# zx80_SD_12_smd_build003.net
KiCad netlist of a schematic drawn in EAGLE
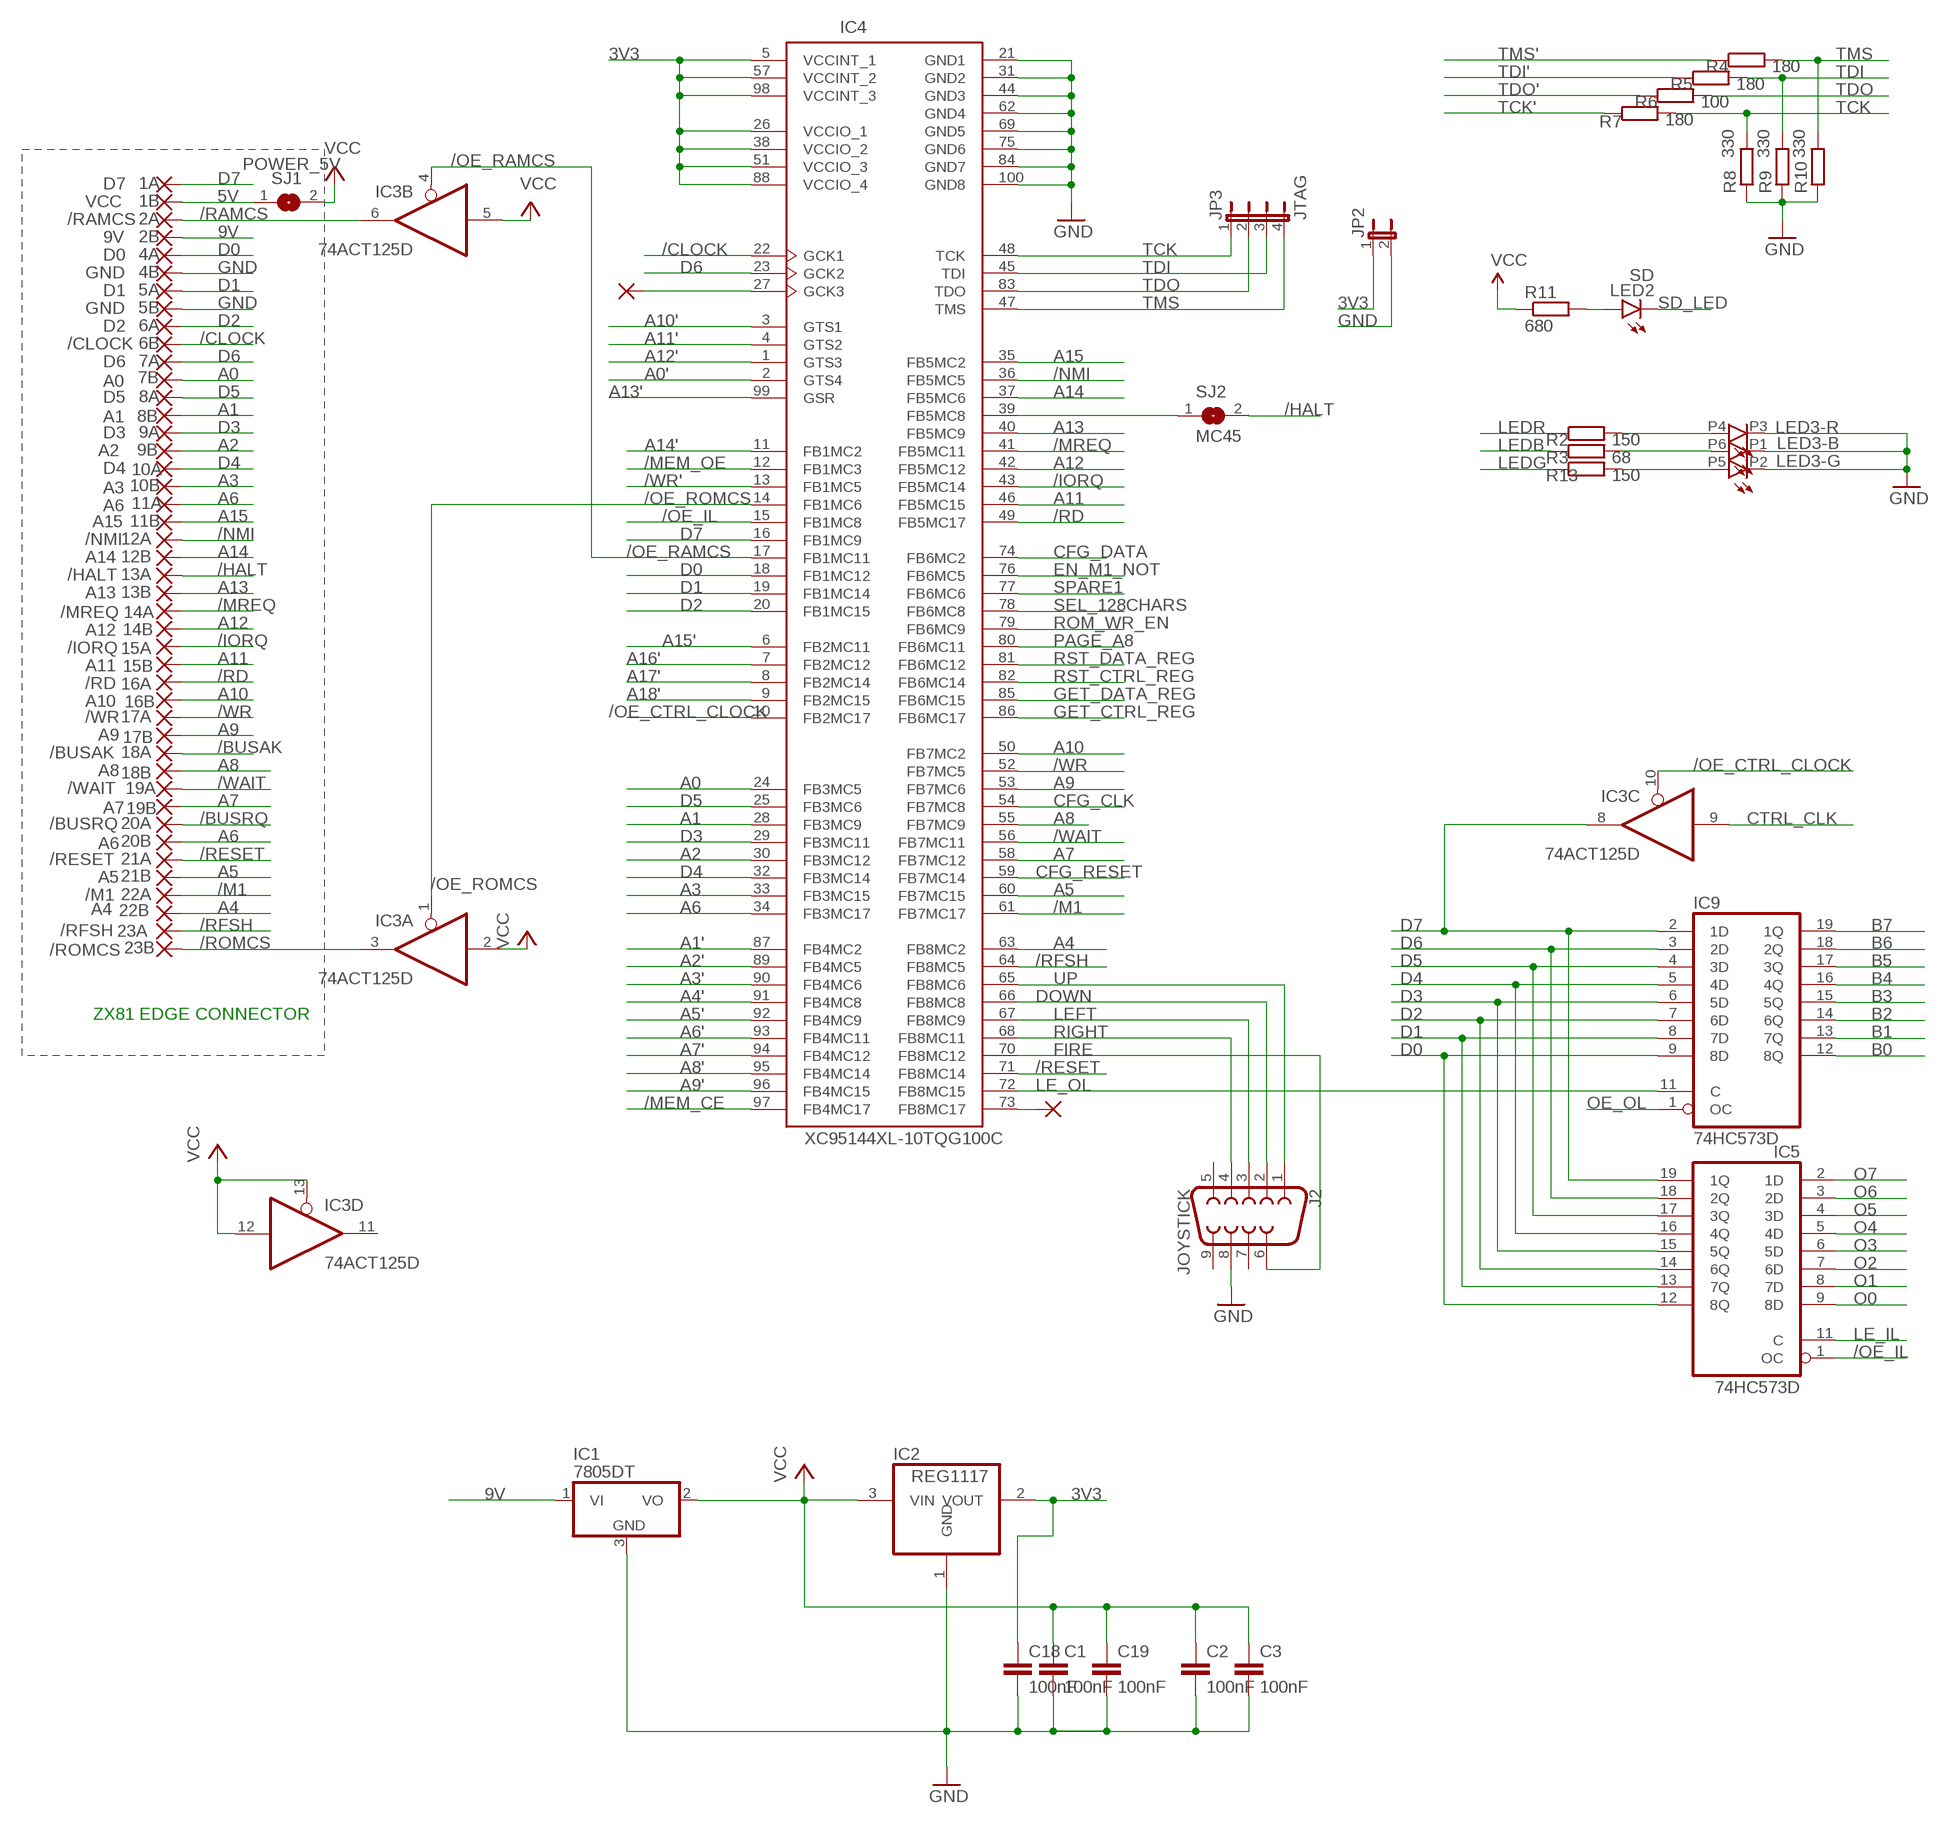
[diagram p0: schematic, sheet 1, part 1 of 2]
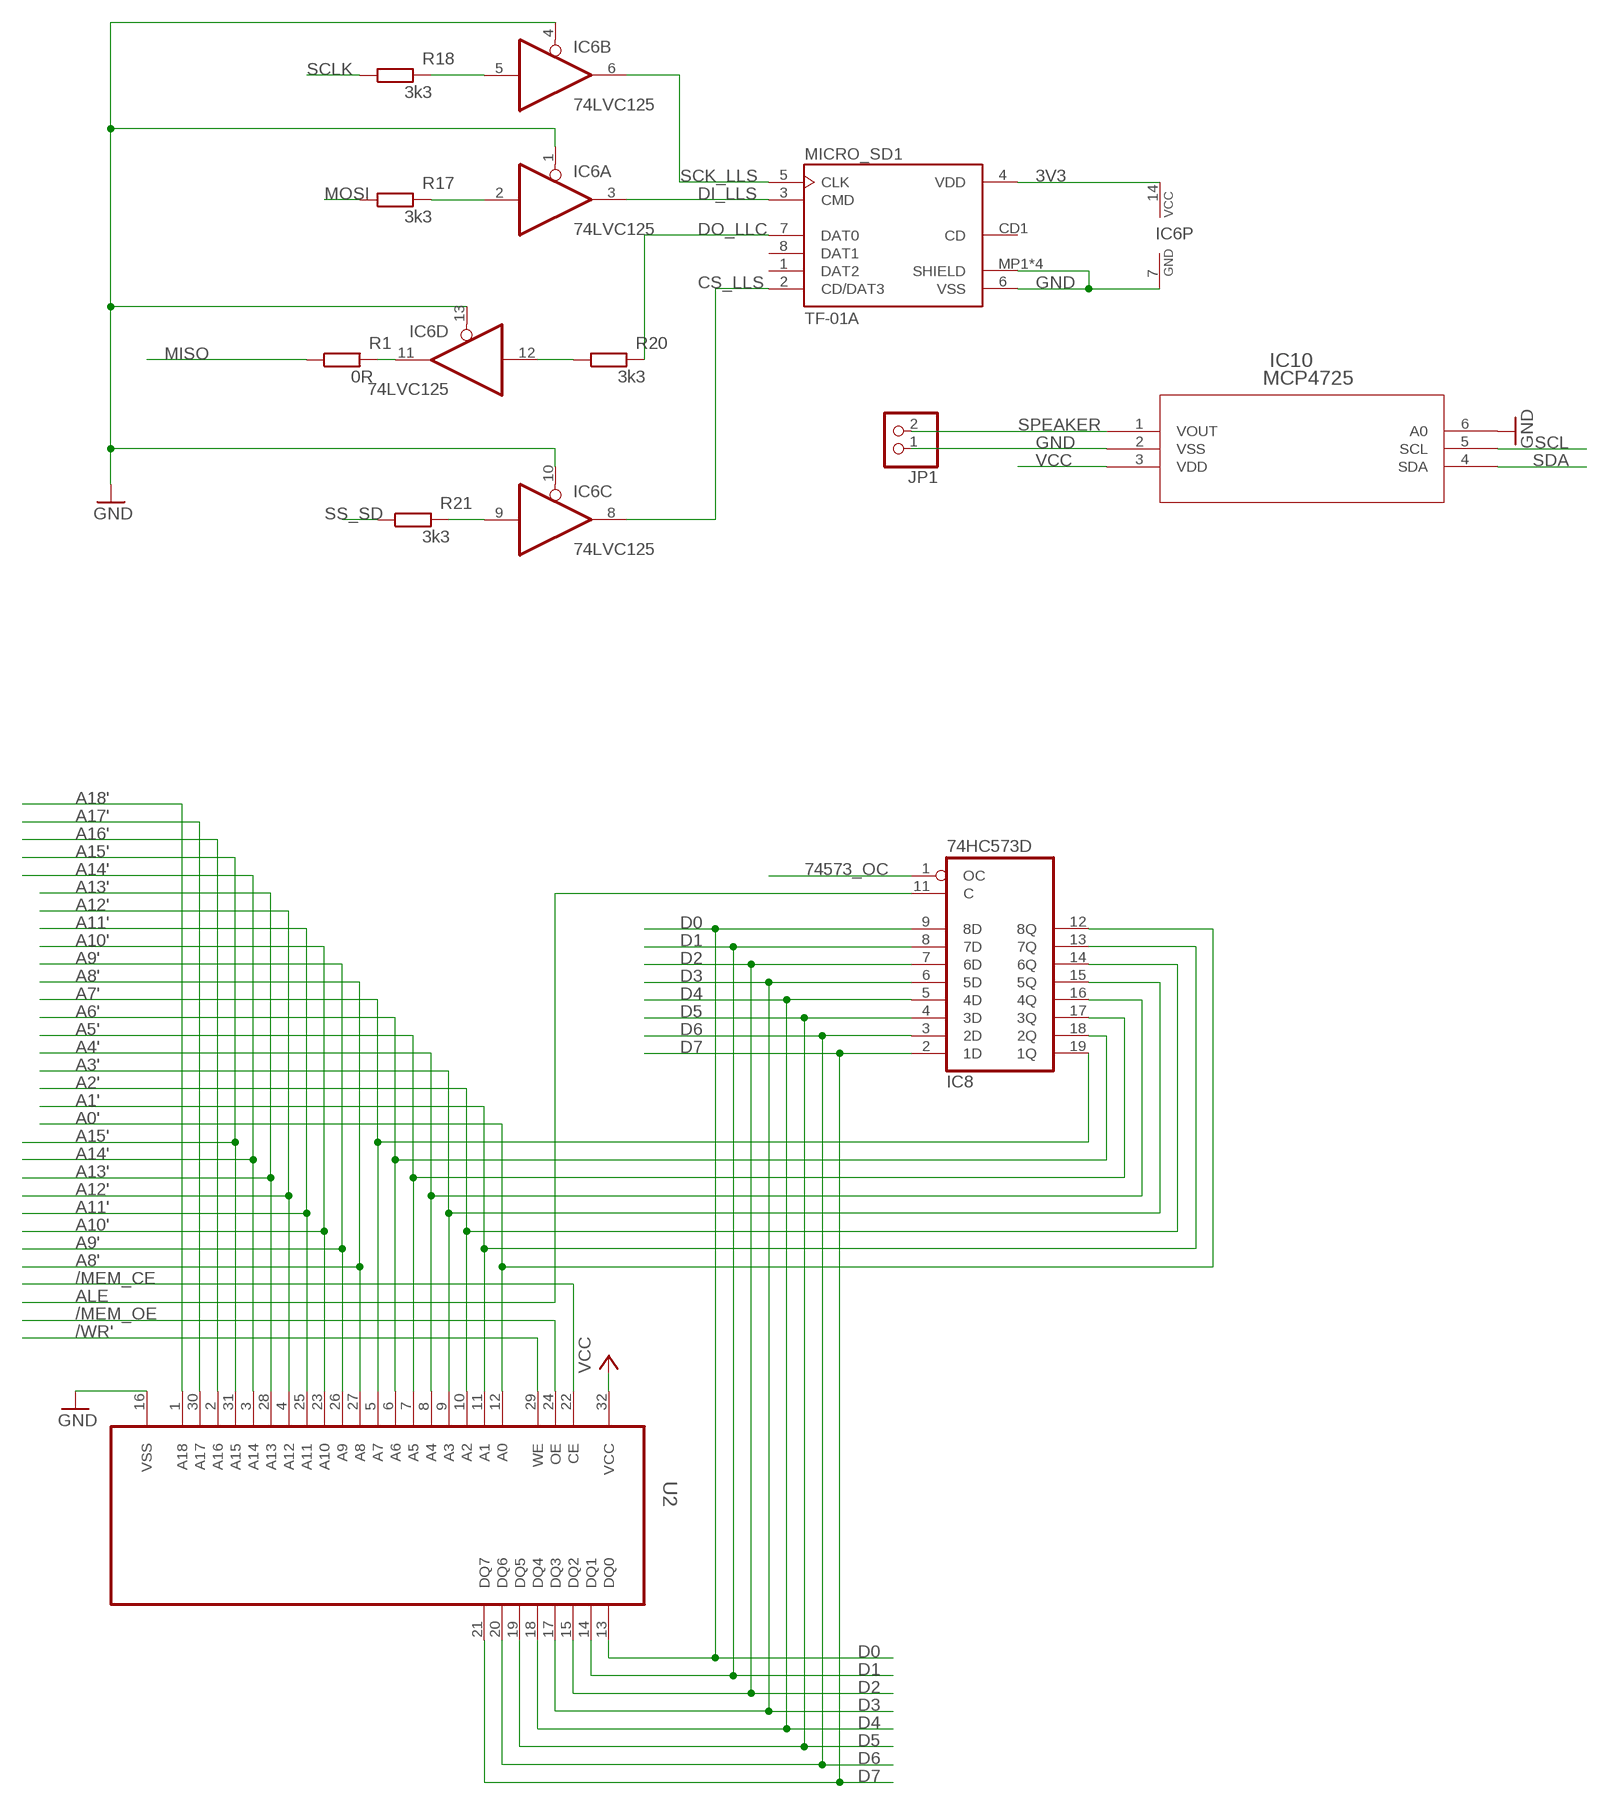
[diagram p1: schematic, sheet 1, part 2 of 2]
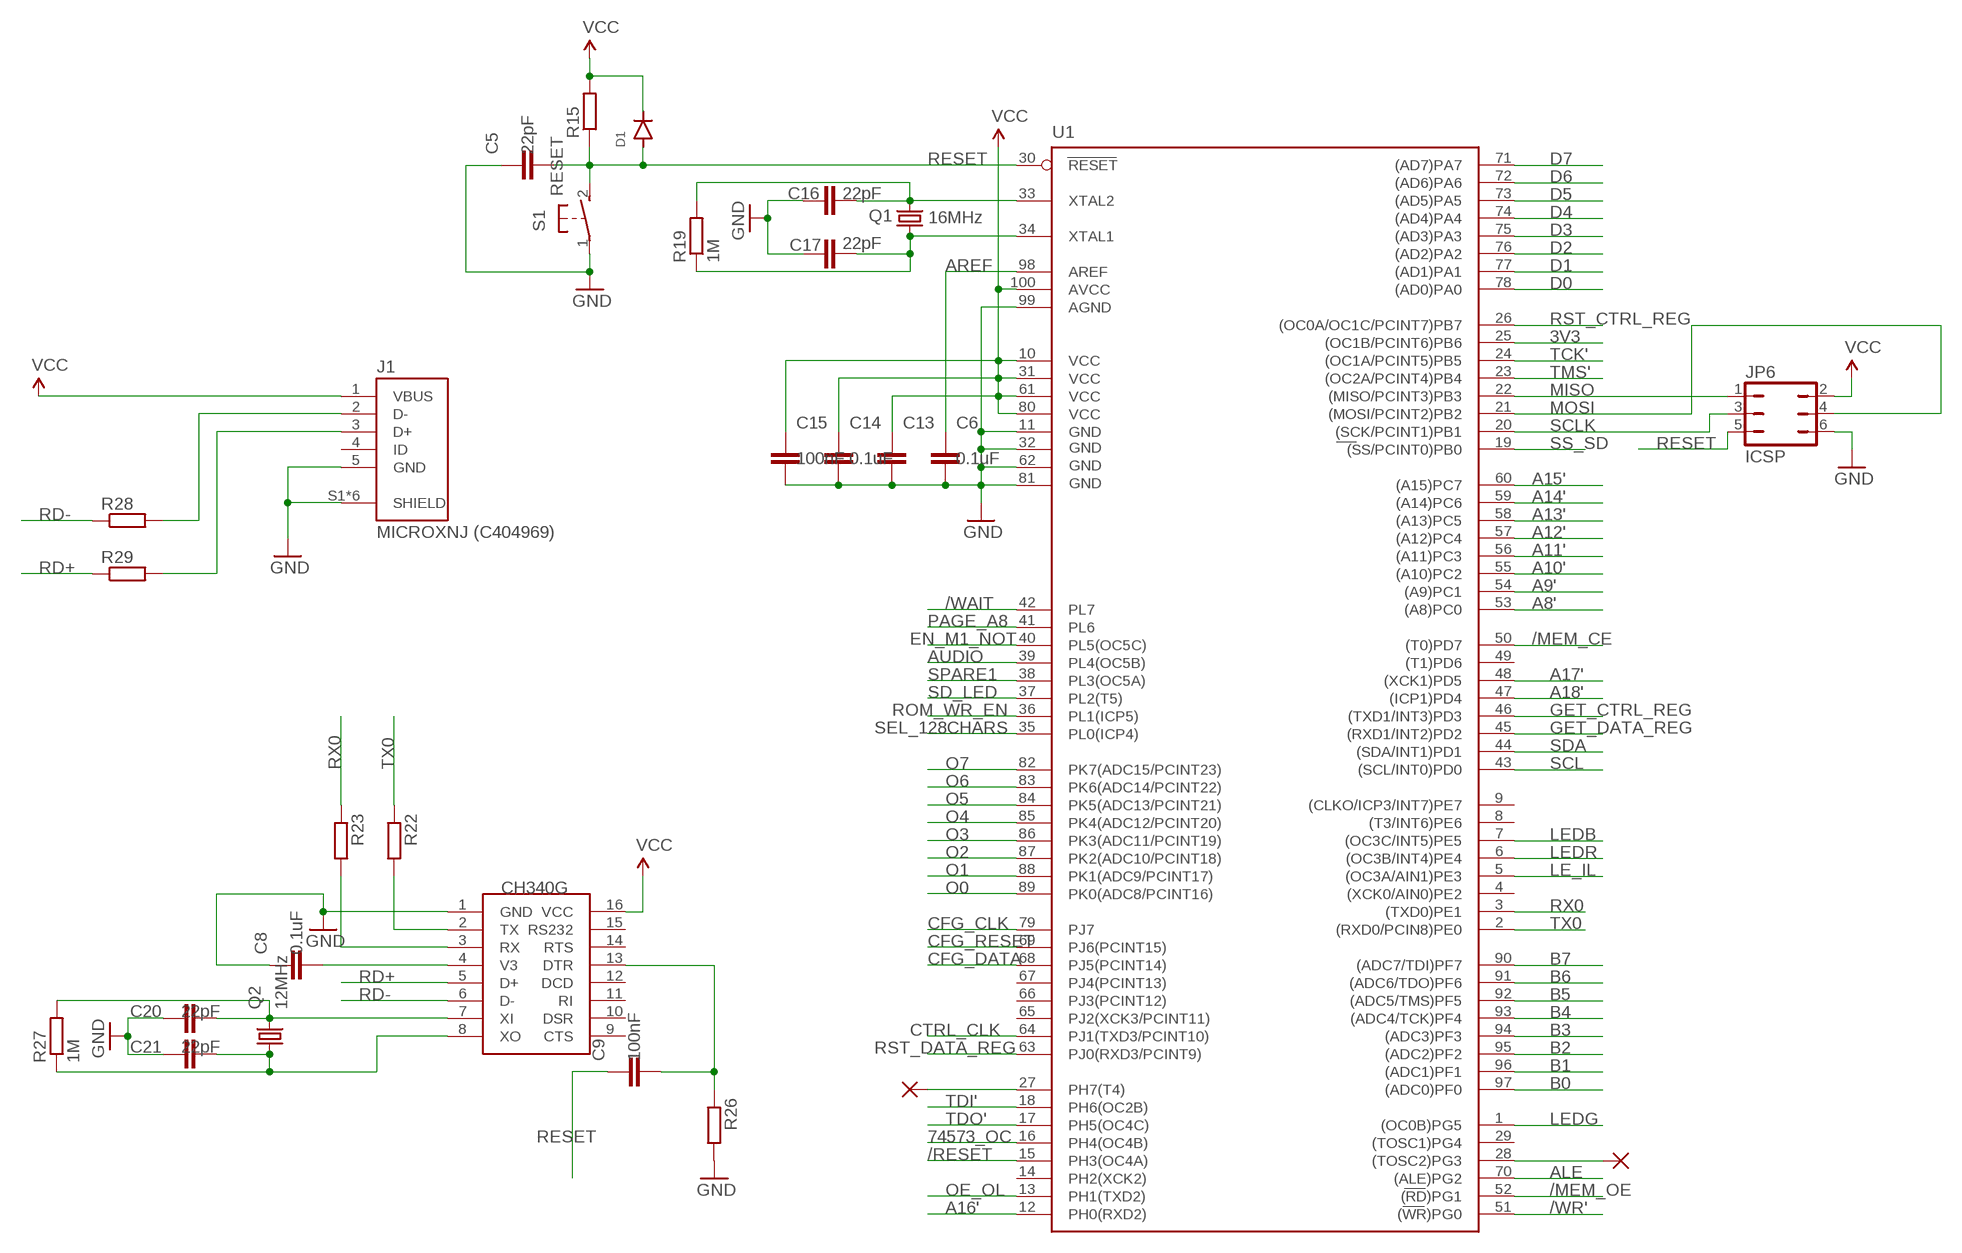
[diagram p2: schematic, sheet 2]

(export (version "E")
  (design (tool "Eeschema 10.0.6"))
  (components
    (comp (ref "C5")
      (value "22pF")
      (footprint "eagle-import:C0603")
      (libsource (lib "eagle-import") (part "C-EUC0603"))
    )
    (comp (ref "C6")
      (value "0.1uF")
      (footprint "eagle-import:C0603")
      (libsource (lib "eagle-import") (part "C-EUC0603"))
    )
    (comp (ref "C8")
      (value "0.1uF")
      (footprint "eagle-import:C0603")
      (libsource (lib "eagle-import") (part "C-EUC0603"))
    )
    (comp (ref "C9")
      (value "100nF")
      (footprint "eagle-import:C0603")
      (libsource (lib "eagle-import") (part "C-EUC0603"))
    )
    (comp (ref "C13")
      (value "0.1uF")
      (footprint "eagle-import:C0603")
      (libsource (lib "eagle-import") (part "C-EUC0603"))
    )
    (comp (ref "C14")
      (value "0.1uF")
      (footprint "eagle-import:C0603")
      (libsource (lib "eagle-import") (part "C-EUC0603"))
    )
    (comp (ref "C15")
      (value "100nF")
      (footprint "eagle-import:C0603")
      (libsource (lib "eagle-import") (part "C-EUC0603"))
    )
    (comp (ref "C16")
      (value "22pF")
      (footprint "eagle-import:C0603")
      (libsource (lib "eagle-import") (part "C-EUC0603"))
    )
    (comp (ref "C17")
      (value "22pF")
      (footprint "eagle-import:C0603")
      (libsource (lib "eagle-import") (part "C-EUC0603"))
    )
    (comp (ref "C20")
      (value "22pF")
      (footprint "eagle-import:C0603")
      (libsource (lib "eagle-import") (part "C-EUC0603"))
    )
    (comp (ref "C21")
      (value "22pF")
      (footprint "eagle-import:C0603")
      (libsource (lib "eagle-import") (part "C-EUC0603"))
    )
    (comp (ref "D1")
      (value "DIODE-SOD123")
      (footprint "eagle-import:SOD123")
      (libsource (lib "eagle-import") (part "DIODE-SOD123"))
    )
    (comp (ref "IC7")
      (value "CH340G")
      (footprint "eagle-import:SOIC16")
      (libsource (lib "eagle-import") (part "CH340G"))
    )
    (comp (ref "J1")
      (value "MICROXNJ (C404969)")
      (footprint "eagle-import:SHOUHAN_MICROXNJ")
      (fields (field (name "MF") "Shouhan") (field (name "MP") "MICROXNJ"))
      (libsource (lib "eagle-import") (part "MICROXNJ"))
    )
    (comp (ref "JP6")
      (value "ICSP")
      (footprint "eagle-import:JP3Q")
      (libsource (lib "eagle-import") (part "JP3Q"))
    )
    (comp (ref "PAD2")
      (value "1,6/0,8")
      (footprint "eagle-import:1,6_0,8")
      (libsource (lib "eagle-import") (part "1,6/0,8"))
    )
    (comp (ref "PAD3")
      (value "1,6/0,8")
      (footprint "eagle-import:1,6_0,8")
      (libsource (lib "eagle-import") (part "1,6/0,8"))
    )
    (comp (ref "Q1")
      (value "16MHz")
      (footprint "eagle-import:3.2X2.5_KX-7")
      (libsource (lib "eagle-import") (part "KX-7"))
    )
    (comp (ref "Q2")
      (value "12MHz")
      (footprint "eagle-import:3.2X2.5_KX-7")
      (libsource (lib "eagle-import") (part "KX-7"))
    )
    (comp (ref "R15")
      (value "R-EU_R0603")
      (footprint "eagle-import:R0603")
      (libsource (lib "eagle-import") (part "rcl_334_R-EU_R0603"))
    )
    (comp (ref "R19")
      (value "1M")
      (footprint "eagle-import:R0603")
      (libsource (lib "eagle-import") (part "rcl_334_R-EU_R0603"))
    )
    (comp (ref "R22")
      (value "1K")
      (footprint "eagle-import:R0603")
      (libsource (lib "eagle-import") (part "rcl_334_R-EU_R0603"))
    )
    (comp (ref "R23")
      (value "1K")
      (footprint "eagle-import:R0603")
      (libsource (lib "eagle-import") (part "rcl_334_R-EU_R0603"))
    )
    (comp (ref "R26")
      (value "1K")
      (footprint "eagle-import:R0603")
      (libsource (lib "eagle-import") (part "rcl_334_R-EU_R0603"))
    )
    (comp (ref "R27")
      (value "1M")
      (footprint "eagle-import:R0603")
      (libsource (lib "eagle-import") (part "rcl_334_R-EU_R0603"))
    )
    (comp (ref "R28")
      (value "22R")
      (footprint "eagle-import:R0603")
      (libsource (lib "eagle-import") (part "rcl_334_R-EU_R0603"))
    )
    (comp (ref "R29")
      (value "22R")
      (footprint "eagle-import:R0603")
      (libsource (lib "eagle-import") (part "rcl_334_R-EU_R0603"))
    )
    (comp (ref "S1")
      (value "RESET")
      (footprint "eagle-import:B3F-31XX")
      (fields (field (name "MPN") "B3F-3100"))
      (libsource (lib "eagle-import") (part "31-XX"))
    )
    (comp (ref "U1")
      (value "ATMEGA2560AU")
      (footprint "eagle-import:TQFP100")
      (libsource (lib "eagle-import") (part "ATMEGA2560AU"))
    )
    (comp (ref "1A")
      (value "D7")
      (footprint "eagle-import:EDGEPIN")
      (libsource (lib "eagle-import") (part "SMD2EDGEPIN"))
    )
    (comp (ref "1B")
      (value "VCC")
      (footprint "eagle-import:EDGEPIN")
      (libsource (lib "eagle-import") (part "SMD2EDGEPIN"))
    )
    (comp (ref "2A")
      (value "/RAMCS")
      (footprint "eagle-import:EDGEPIN")
      (libsource (lib "eagle-import") (part "SMD2EDGEPIN"))
    )
    (comp (ref "2B")
      (value "9V")
      (footprint "eagle-import:EDGEPIN")
      (libsource (lib "eagle-import") (part "SMD2EDGEPIN"))
    )
    (comp (ref "4A")
      (value "D0")
      (footprint "eagle-import:EDGEPIN")
      (libsource (lib "eagle-import") (part "SMD2EDGEPIN"))
    )
    (comp (ref "4B")
      (value "GND")
      (footprint "eagle-import:EDGEPIN")
      (libsource (lib "eagle-import") (part "SMD2EDGEPIN"))
    )
    (comp (ref "5A")
      (value "D1")
      (footprint "eagle-import:EDGEPIN")
      (libsource (lib "eagle-import") (part "SMD2EDGEPIN"))
    )
    (comp (ref "5B")
      (value "GND")
      (footprint "eagle-import:EDGEPIN")
      (libsource (lib "eagle-import") (part "SMD2EDGEPIN"))
    )
    (comp (ref "6A")
      (value "D2")
      (footprint "eagle-import:EDGEPIN")
      (libsource (lib "eagle-import") (part "SMD2EDGEPIN"))
    )
    (comp (ref "6B")
      (value "/CLOCK")
      (footprint "eagle-import:EDGEPIN")
      (libsource (lib "eagle-import") (part "SMD2EDGEPIN"))
    )
    (comp (ref "7A")
      (value "D6")
      (footprint "eagle-import:EDGEPIN")
      (libsource (lib "eagle-import") (part "SMD2EDGEPIN"))
    )
    (comp (ref "7B")
      (value "A0")
      (footprint "eagle-import:EDGEPIN")
      (libsource (lib "eagle-import") (part "SMD2EDGEPIN"))
    )
    (comp (ref "8A")
      (value "D5")
      (footprint "eagle-import:EDGEPIN")
      (libsource (lib "eagle-import") (part "SMD2EDGEPIN"))
    )
    (comp (ref "8B")
      (value "A1")
      (footprint "eagle-import:EDGEPIN")
      (libsource (lib "eagle-import") (part "SMD2EDGEPIN"))
    )
    (comp (ref "9A")
      (value "D3")
      (footprint "eagle-import:EDGEPIN")
      (libsource (lib "eagle-import") (part "SMD2EDGEPIN"))
    )
    (comp (ref "9B")
      (value "A2")
      (footprint "eagle-import:EDGEPIN")
      (libsource (lib "eagle-import") (part "SMD2EDGEPIN"))
    )
    (comp (ref "10A")
      (value "D4")
      (footprint "eagle-import:EDGEPIN")
      (libsource (lib "eagle-import") (part "SMD2EDGEPIN"))
    )
    (comp (ref "10B")
      (value "A3")
      (footprint "eagle-import:EDGEPIN")
      (libsource (lib "eagle-import") (part "SMD2EDGEPIN"))
    )
    (comp (ref "11A")
      (value "A6")
      (footprint "eagle-import:EDGEPIN")
      (libsource (lib "eagle-import") (part "SMD2EDGEPIN"))
    )
    (comp (ref "11B")
      (value "A15")
      (footprint "eagle-import:EDGEPIN")
      (libsource (lib "eagle-import") (part "SMD2EDGEPIN"))
    )
    (comp (ref "12A")
      (value "/NMI")
      (footprint "eagle-import:EDGEPIN")
      (libsource (lib "eagle-import") (part "SMD2EDGEPIN"))
    )
    (comp (ref "12B")
      (value "A14")
      (footprint "eagle-import:EDGEPIN")
      (libsource (lib "eagle-import") (part "SMD2EDGEPIN"))
    )
    (comp (ref "13A")
      (value "/HALT")
      (footprint "eagle-import:EDGEPIN")
      (libsource (lib "eagle-import") (part "SMD2EDGEPIN"))
    )
    (comp (ref "13B")
      (value "A13")
      (footprint "eagle-import:EDGEPIN")
      (libsource (lib "eagle-import") (part "SMD2EDGEPIN"))
    )
    (comp (ref "14A")
      (value "/MREQ")
      (footprint "eagle-import:EDGEPIN")
      (libsource (lib "eagle-import") (part "SMD2EDGEPIN"))
    )
    (comp (ref "14B")
      (value "A12")
      (footprint "eagle-import:EDGEPIN")
      (libsource (lib "eagle-import") (part "SMD2EDGEPIN"))
    )
    (comp (ref "15A")
      (value "/IORQ")
      (footprint "eagle-import:EDGEPIN")
      (libsource (lib "eagle-import") (part "SMD2EDGEPIN"))
    )
    (comp (ref "15B")
      (value "A11")
      (footprint "eagle-import:EDGEPIN")
      (libsource (lib "eagle-import") (part "SMD2EDGEPIN"))
    )
    (comp (ref "16A")
      (value "/RD")
      (footprint "eagle-import:EDGEPIN")
      (libsource (lib "eagle-import") (part "SMD2EDGEPIN"))
    )
    (comp (ref "16B")
      (value "A10")
      (footprint "eagle-import:EDGEPIN")
      (libsource (lib "eagle-import") (part "SMD2EDGEPIN"))
    )
    (comp (ref "17A")
      (value "/WR")
      (footprint "eagle-import:EDGEPIN")
      (libsource (lib "eagle-import") (part "SMD2EDGEPIN"))
    )
    (comp (ref "17B")
      (value "A9")
      (footprint "eagle-import:EDGEPIN")
      (libsource (lib "eagle-import") (part "SMD2EDGEPIN"))
    )
    (comp (ref "18A")
      (value "/BUSAK")
      (footprint "eagle-import:EDGEPIN")
      (libsource (lib "eagle-import") (part "SMD2EDGEPIN"))
    )
    (comp (ref "18B")
      (value "A8")
      (footprint "eagle-import:EDGEPIN")
      (libsource (lib "eagle-import") (part "SMD2EDGEPIN"))
    )
    (comp (ref "19A")
      (value "/WAIT")
      (footprint "eagle-import:EDGEPIN")
      (libsource (lib "eagle-import") (part "SMD2EDGEPIN"))
    )
    (comp (ref "19B")
      (value "A7")
      (footprint "eagle-import:EDGEPIN")
      (libsource (lib "eagle-import") (part "SMD2EDGEPIN"))
    )
    (comp (ref "20A")
      (value "/BUSRQ")
      (footprint "eagle-import:EDGEPIN")
      (libsource (lib "eagle-import") (part "SMD2EDGEPIN"))
    )
    (comp (ref "20B")
      (value "A6")
      (footprint "eagle-import:EDGEPIN")
      (libsource (lib "eagle-import") (part "SMD2EDGEPIN"))
    )
    (comp (ref "21A")
      (value "/RESET")
      (footprint "eagle-import:EDGEPIN")
      (libsource (lib "eagle-import") (part "SMD2EDGEPIN"))
    )
    (comp (ref "21B")
      (value "A5")
      (footprint "eagle-import:EDGEPIN")
      (libsource (lib "eagle-import") (part "SMD2EDGEPIN"))
    )
    (comp (ref "22A")
      (value "/M1")
      (footprint "eagle-import:EDGEPIN")
      (libsource (lib "eagle-import") (part "SMD2EDGEPIN"))
    )
    (comp (ref "22B")
      (value "A4")
      (footprint "eagle-import:EDGEPIN")
      (libsource (lib "eagle-import") (part "SMD2EDGEPIN"))
    )
    (comp (ref "23A")
      (value "/RFSH")
      (footprint "eagle-import:EDGEPIN")
      (libsource (lib "eagle-import") (part "SMD2EDGEPIN"))
    )
    (comp (ref "23B")
      (value "/ROMCS")
      (footprint "eagle-import:EDGEPIN")
      (libsource (lib "eagle-import") (part "SMD2EDGEPIN"))
    )
    (comp (ref "C1")
      (value "100nF")
      (footprint "eagle-import:C0603")
      (libsource (lib "eagle-import") (part "C-EUC0603"))
    )
    (comp (ref "C2")
      (value "100nF")
      (footprint "eagle-import:C0603")
      (libsource (lib "eagle-import") (part "C-EUC0603"))
    )
    (comp (ref "C3")
      (value "100nF")
      (footprint "eagle-import:C0603")
      (libsource (lib "eagle-import") (part "C-EUC0603"))
    )
    (comp (ref "C18")
      (value "100nF")
      (footprint "eagle-import:C0603")
      (libsource (lib "eagle-import") (part "C-EUC0603"))
    )
    (comp (ref "C19")
      (value "100nF")
      (footprint "eagle-import:C0603")
      (libsource (lib "eagle-import") (part "C-EUC0603"))
    )
    (comp (ref "IC1")
      (value "7805DT")
      (footprint "eagle-import:TO252")
      (libsource (lib "eagle-import") (part "78DT05"))
    )
    (comp (ref "IC2")
      (value "REG1117")
      (footprint "eagle-import:SOT223")
      (libsource (lib "eagle-import") (part "REG1117"))
    )
    (comp (ref "IC3")
      (value "74ACT125D")
      (footprint "eagle-import:SO14")
      (libsource (lib "eagle-import") (part "74125DACT"))
    )
    (comp (ref "IC4")
      (value "XC95144XL-10TQG100C")
      (footprint "eagle-import:TQFP100")
      (fields (field (name "MF") "Xilinx Inc."))
      (libsource (lib "eagle-import") (part "XC95144XL-10TQG100C"))
    )
    (comp (ref "IC5")
      (value "74HC573D")
      (footprint "eagle-import:SO20W")
      (libsource (lib "eagle-import") (part "74573DHC"))
    )
    (comp (ref "IC6")
      (value "74LVC125")
      (footprint "eagle-import:SO14")
      (libsource (lib "eagle-import") (part "74125DLS"))
    )
    (comp (ref "IC8")
      (value "74HC573D")
      (footprint "eagle-import:SO20W")
      (libsource (lib "eagle-import") (part "74573DHC"))
    )
    (comp (ref "IC9")
      (value "74HC573D")
      (footprint "eagle-import:SO20W")
      (libsource (lib "eagle-import") (part "74573DHC"))
    )
    (comp (ref "IC10")
      (value "MCP4725")
      (footprint "eagle-import:SOT-23-6_MC")
      (fields (field (name "MF") "Microchip") (field (name "MP") "MCP4725A2T-E/CH"))
      (libsource (lib "eagle-import") (part "MCP4725A2T-E/CH"))
    )
    (comp (ref "J2")
      (value "JOYSTICK")
      (footprint "eagle-import:DB9_MALE")
      (libsource (lib "eagle-import") (part "DB9MALE"))
    )
    (comp (ref "JP1")
      (value "PINHD-1X2")
      (footprint "eagle-import:1X02")
      (libsource (lib "eagle-import") (part "PINHD-1X2"))
    )
    (comp (ref "JP2")
      (value "JP1E")
      (footprint "eagle-import:JP1")
      (libsource (lib "eagle-import") (part "JP1E"))
    )
    (comp (ref "JP3")
      (value "JTAG")
      (footprint "eagle-import:JP4")
      (libsource (lib "eagle-import") (part "JP4E"))
    )
    (comp (ref "LED2")
      (value "SD")
      (footprint "eagle-import:CHIPLED_0603")
      (libsource (lib "eagle-import") (part "LEDCHIPLED_0603"))
    )
    (comp (ref "LED3")
      (value "STATUS")
      (footprint "eagle-import:3535-PLCC6")
      (libsource (lib "eagle-import") (part "3535RGB3535RGB"))
    )
    (comp (ref "MICRO_SD1")
      (value "TF-01A")
      (footprint "eagle-import:TF-01A")
      (fields (field (name "MF") "HRO Electronics Co., Ltd."))
      (libsource (lib "eagle-import") (part "TF-01A"))
    )
    (comp (ref "PAD1")
      (value "1,6/0,8")
      (footprint "eagle-import:1,6_0,8")
      (libsource (lib "eagle-import") (part "1,6/0,8"))
    )
    (comp (ref "PAD6")
      (value "P73")
      (footprint "eagle-import:1,6_0,8")
      (libsource (lib "eagle-import") (part "1,6/0,8"))
    )
    (comp (ref "R1")
      (value "0R")
      (footprint "eagle-import:R0603")
      (libsource (lib "eagle-import") (part "R-EU_R0603"))
    )
    (comp (ref "R2")
      (value "150")
      (footprint "eagle-import:R0603")
      (libsource (lib "eagle-import") (part "rcl_334_R-EU_R0603"))
    )
    (comp (ref "R3")
      (value "68")
      (footprint "eagle-import:R0603")
      (libsource (lib "eagle-import") (part "rcl_334_R-EU_R0603"))
    )
    (comp (ref "R4")
      (value "180")
      (footprint "eagle-import:R0603")
      (libsource (lib "eagle-import") (part "rcl_334_R-EU_R0603"))
    )
    (comp (ref "R5")
      (value "180")
      (footprint "eagle-import:R0603")
      (libsource (lib "eagle-import") (part "rcl_334_R-EU_R0603"))
    )
    (comp (ref "R6")
      (value "100")
      (footprint "eagle-import:R0603")
      (libsource (lib "eagle-import") (part "rcl_334_R-EU_R0603"))
    )
    (comp (ref "R7")
      (value "180")
      (footprint "eagle-import:R0603")
      (libsource (lib "eagle-import") (part "rcl_334_R-EU_R0603"))
    )
    (comp (ref "R8")
      (value "330")
      (footprint "eagle-import:R0603")
      (libsource (lib "eagle-import") (part "rcl_334_R-EU_R0603"))
    )
    (comp (ref "R9")
      (value "330")
      (footprint "eagle-import:R0603")
      (libsource (lib "eagle-import") (part "rcl_334_R-EU_R0603"))
    )
    (comp (ref "R10")
      (value "330")
      (footprint "eagle-import:R0603")
      (libsource (lib "eagle-import") (part "rcl_334_R-EU_R0603"))
    )
    (comp (ref "R11")
      (value "680")
      (footprint "eagle-import:R0603")
      (libsource (lib "eagle-import") (part "R-EU_R0603"))
    )
    (comp (ref "R13")
      (value "150")
      (footprint "eagle-import:R0603")
      (libsource (lib "eagle-import") (part "rcl_334_R-EU_R0603"))
    )
    (comp (ref "R17")
      (value "3k3")
      (footprint "eagle-import:R0603")
      (libsource (lib "eagle-import") (part "R-EU_R0603"))
    )
    (comp (ref "R18")
      (value "3k3")
      (footprint "eagle-import:R0603")
      (libsource (lib "eagle-import") (part "R-EU_R0603"))
    )
    (comp (ref "R20")
      (value "3k3")
      (footprint "eagle-import:R0603")
      (libsource (lib "eagle-import") (part "R-EU_R0603"))
    )
    (comp (ref "R21")
      (value "3k3")
      (footprint "eagle-import:R0603")
      (libsource (lib "eagle-import") (part "R-EU_R0603"))
    )
    (comp (ref "SJ1")
      (value "POWER_5V")
      (footprint "eagle-import:SJ")
      (libsource (lib "eagle-import") (part "SJ"))
    )
    (comp (ref "SJ2")
      (value "MC45")
      (footprint "eagle-import:SJ")
      (libsource (lib "eagle-import") (part "SJ"))
    )
    (comp (ref "U2")
      (value "AS6C4008")
      (footprint "eagle-import:SOP32-5")
      (libsource (lib "eagle-import") (part "AS6C4008-55SINSOP5"))
    )
  )
  (nets
    (net (code "1") (name "3V3") (class "Default")
      (node (ref "C18") (pin "1") (pinfunction "1_1") (pintype "passive"))
      (node (ref "IC2") (pin "2") (pinfunction "VOUT_2") (pintype "output"))
      (node (ref "IC4") (pin "26") (pinfunction "VCCIO_1_26") (pintype "power_in"))
      (node (ref "IC4") (pin "38") (pinfunction "VCCIO_2_38") (pintype "power_in"))
      (node (ref "IC4") (pin "5") (pinfunction "VCCINT_1_5") (pintype "power_in"))
      (node (ref "IC4") (pin "51") (pinfunction "VCCIO_3_51") (pintype "power_in"))
      (node (ref "IC4") (pin "57") (pinfunction "VCCINT_2_57") (pintype "power_in"))
      (node (ref "IC4") (pin "88") (pinfunction "VCCIO_4_88") (pintype "power_in"))
      (node (ref "IC4") (pin "98") (pinfunction "VCCINT_3_98") (pintype "power_in"))
      (node (ref "IC6") (pin "14") (pinfunction "VCC_14") (pintype "power_in"))
      (node (ref "JP2") (pin "1") (pinfunction "1_1") (pintype "passive"))
      (node (ref "MICRO_SD1") (pin "4") (pinfunction "VDD_4") (pintype "power_in"))
      (node (ref "U1") (pin "25") (pinfunction "(OC1B/PCINT6)PB6_25") (pintype "bidirectional"))
    )
    (net (code "2") (name "5V") (class "Default")
      (node (ref "1B") (pin "1") (pinfunction "P_1") (pintype "passive"))
      (node (ref "SJ1") (pin "1") (pinfunction "1_1") (pintype "passive"))
    )
    (net (code "3") (name "9V") (class "Default")
      (node (ref "2B") (pin "1") (pinfunction "P_1") (pintype "passive"))
      (node (ref "IC1") (pin "1") (pinfunction "VI_1") (pintype "input"))
    )
    (net (code "4") (name "74573_OC") (class "Default")
      (node (ref "IC8") (pin "1") (pinfunction "OC_1") (pintype "input"))
      (node (ref "U1") (pin "16") (pinfunction "PH4(OC4B)_16") (pintype "bidirectional"))
    )
    (net (code "5") (name "A0") (class "Default")
      (node (ref "7B") (pin "1") (pinfunction "P_1") (pintype "passive"))
      (node (ref "IC4") (pin "24") (pinfunction "FB3MC5_24") (pintype "bidirectional"))
    )
    (net (code "6") (name "A0'") (class "Default")
      (node (ref "IC4") (pin "2") (pinfunction "GTS4_2") (pintype "bidirectional"))
      (node (ref "IC8") (pin "12") (pinfunction "8Q_12") (pintype "tri_state"))
      (node (ref "U2") (pin "12") (pinfunction "A0_12") (pintype "input"))
    )
    (net (code "7") (name "A1") (class "Default")
      (node (ref "8B") (pin "1") (pinfunction "P_1") (pintype "passive"))
      (node (ref "IC4") (pin "28") (pinfunction "FB3MC9_28") (pintype "bidirectional"))
    )
    (net (code "8") (name "A1'") (class "Default")
      (node (ref "IC4") (pin "87") (pinfunction "FB4MC2_87") (pintype "bidirectional"))
      (node (ref "IC8") (pin "13") (pinfunction "7Q_13") (pintype "tri_state"))
      (node (ref "U2") (pin "11") (pinfunction "A1_11") (pintype "input"))
    )
    (net (code "9") (name "A2") (class "Default")
      (node (ref "9B") (pin "1") (pinfunction "P_1") (pintype "passive"))
      (node (ref "IC4") (pin "30") (pinfunction "FB3MC12_30") (pintype "bidirectional"))
    )
    (net (code "10") (name "A2'") (class "Default")
      (node (ref "IC4") (pin "89") (pinfunction "FB4MC5_89") (pintype "bidirectional"))
      (node (ref "IC8") (pin "14") (pinfunction "6Q_14") (pintype "tri_state"))
      (node (ref "U2") (pin "10") (pinfunction "A2_10") (pintype "input"))
    )
    (net (code "11") (name "A3") (class "Default")
      (node (ref "10B") (pin "1") (pinfunction "P_1") (pintype "passive"))
      (node (ref "IC4") (pin "33") (pinfunction "FB3MC15_33") (pintype "bidirectional"))
    )
    (net (code "12") (name "A3'") (class "Default")
      (node (ref "IC4") (pin "90") (pinfunction "FB4MC6_90") (pintype "bidirectional"))
      (node (ref "IC8") (pin "15") (pinfunction "5Q_15") (pintype "tri_state"))
      (node (ref "U2") (pin "9") (pinfunction "A3_9") (pintype "input"))
    )
    (net (code "13") (name "A4") (class "Default")
      (node (ref "22B") (pin "1") (pinfunction "P_1") (pintype "passive"))
      (node (ref "IC4") (pin "63") (pinfunction "FB8MC2_63") (pintype "bidirectional"))
    )
    (net (code "14") (name "A4'") (class "Default")
      (node (ref "IC4") (pin "91") (pinfunction "FB4MC8_91") (pintype "bidirectional"))
      (node (ref "IC8") (pin "16") (pinfunction "4Q_16") (pintype "tri_state"))
      (node (ref "U2") (pin "8") (pinfunction "A4_8") (pintype "input"))
    )
    (net (code "15") (name "A5") (class "Default")
      (node (ref "21B") (pin "1") (pinfunction "P_1") (pintype "passive"))
      (node (ref "IC4") (pin "60") (pinfunction "FB7MC15_60") (pintype "bidirectional"))
    )
    (net (code "16") (name "A5'") (class "Default")
      (node (ref "IC4") (pin "92") (pinfunction "FB4MC9_92") (pintype "bidirectional"))
      (node (ref "IC8") (pin "17") (pinfunction "3Q_17") (pintype "tri_state"))
      (node (ref "U2") (pin "7") (pinfunction "A5_7") (pintype "input"))
    )
    (net (code "17") (name "A6") (class "Default")
      (node (ref "11A") (pin "1") (pinfunction "P_1") (pintype "passive"))
      (node (ref "20B") (pin "1") (pinfunction "P_1") (pintype "passive"))
      (node (ref "IC4") (pin "34") (pinfunction "FB3MC17_34") (pintype "bidirectional"))
    )
    (net (code "18") (name "A6'") (class "Default")
      (node (ref "IC4") (pin "93") (pinfunction "FB4MC11_93") (pintype "bidirectional"))
      (node (ref "IC8") (pin "18") (pinfunction "2Q_18") (pintype "tri_state"))
      (node (ref "U2") (pin "6") (pinfunction "A6_6") (pintype "input"))
    )
    (net (code "19") (name "A7") (class "Default")
      (node (ref "19B") (pin "1") (pinfunction "P_1") (pintype "passive"))
      (node (ref "IC4") (pin "58") (pinfunction "FB7MC12_58") (pintype "bidirectional"))
    )
    (net (code "20") (name "A7'") (class "Default")
      (node (ref "IC4") (pin "94") (pinfunction "FB4MC12_94") (pintype "bidirectional"))
      (node (ref "IC8") (pin "19") (pinfunction "1Q_19") (pintype "tri_state"))
      (node (ref "U2") (pin "5") (pinfunction "A7_5") (pintype "input"))
    )
    (net (code "21") (name "A8") (class "Default")
      (node (ref "18B") (pin "1") (pinfunction "P_1") (pintype "passive"))
      (node (ref "IC4") (pin "55") (pinfunction "FB7MC9_55") (pintype "bidirectional"))
    )
    (net (code "22") (name "A8'") (class "Default")
      (node (ref "IC4") (pin "95") (pinfunction "FB4MC14_95") (pintype "bidirectional"))
      (node (ref "U1") (pin "53") (pinfunction "(A8)PC0_53") (pintype "bidirectional"))
      (node (ref "U2") (pin "27") (pinfunction "A8_27") (pintype "input"))
    )
    (net (code "23") (name "A9") (class "Default")
      (node (ref "17B") (pin "1") (pinfunction "P_1") (pintype "passive"))
      (node (ref "IC4") (pin "53") (pinfunction "FB7MC6_53") (pintype "bidirectional"))
    )
    (net (code "24") (name "A9'") (class "Default")
      (node (ref "IC4") (pin "96") (pinfunction "FB4MC15_96") (pintype "bidirectional"))
      (node (ref "U1") (pin "54") (pinfunction "(A9)PC1_54") (pintype "bidirectional"))
      (node (ref "U2") (pin "26") (pinfunction "A9_26") (pintype "input"))
    )
    (net (code "25") (name "A10") (class "Default")
      (node (ref "16B") (pin "1") (pinfunction "P_1") (pintype "passive"))
      (node (ref "IC4") (pin "50") (pinfunction "FB7MC2_50") (pintype "bidirectional"))
    )
    (net (code "26") (name "A10'") (class "Default")
      (node (ref "IC4") (pin "3") (pinfunction "GTS1_3") (pintype "bidirectional"))
      (node (ref "U1") (pin "55") (pinfunction "(A10)PC2_55") (pintype "bidirectional"))
      (node (ref "U2") (pin "23") (pinfunction "A10_23") (pintype "input"))
    )
    (net (code "27") (name "A11") (class "Default")
      (node (ref "15B") (pin "1") (pinfunction "P_1") (pintype "passive"))
      (node (ref "IC4") (pin "46") (pinfunction "FB5MC15_46") (pintype "bidirectional"))
    )
    (net (code "28") (name "A11'") (class "Default")
      (node (ref "IC4") (pin "4") (pinfunction "GTS2_4") (pintype "bidirectional"))
      (node (ref "U1") (pin "56") (pinfunction "(A11)PC3_56") (pintype "bidirectional"))
      (node (ref "U2") (pin "25") (pinfunction "A11_25") (pintype "input"))
    )
    (net (code "29") (name "A12") (class "Default")
      (node (ref "14B") (pin "1") (pinfunction "P_1") (pintype "passive"))
      (node (ref "IC4") (pin "42") (pinfunction "FB5MC12_42") (pintype "bidirectional"))
    )
    (net (code "30") (name "A12'") (class "Default")
      (node (ref "IC4") (pin "1") (pinfunction "GTS3_1") (pintype "bidirectional"))
      (node (ref "U1") (pin "57") (pinfunction "(A12)PC4_57") (pintype "bidirectional"))
      (node (ref "U2") (pin "4") (pinfunction "A12_4") (pintype "input"))
    )
    (net (code "31") (name "A13") (class "Default")
      (node (ref "13B") (pin "1") (pinfunction "P_1") (pintype "passive"))
      (node (ref "IC4") (pin "40") (pinfunction "FB5MC9_40") (pintype "bidirectional"))
    )
    (net (code "32") (name "A13'") (class "Default")
      (node (ref "IC4") (pin "99") (pinfunction "GSR_99") (pintype "bidirectional"))
      (node (ref "U1") (pin "58") (pinfunction "(A13)PC5_58") (pintype "bidirectional"))
      (node (ref "U2") (pin "28") (pinfunction "A13_28") (pintype "input"))
    )
    (net (code "33") (name "A14") (class "Default")
      (node (ref "12B") (pin "1") (pinfunction "P_1") (pintype "passive"))
      (node (ref "IC4") (pin "37") (pinfunction "FB5MC6_37") (pintype "bidirectional"))
    )
    (net (code "34") (name "A14'") (class "Default")
      (node (ref "IC4") (pin "11") (pinfunction "FB1MC2_11") (pintype "bidirectional"))
      (node (ref "U1") (pin "59") (pinfunction "(A14)PC6_59") (pintype "bidirectional"))
      (node (ref "U2") (pin "3") (pinfunction "A14_3") (pintype "input"))
    )
    (net (code "35") (name "A15") (class "Default")
      (node (ref "11B") (pin "1") (pinfunction "P_1") (pintype "passive"))
      (node (ref "IC4") (pin "35") (pinfunction "FB5MC2_35") (pintype "bidirectional"))
    )
    (net (code "36") (name "A15'") (class "Default")
      (node (ref "IC4") (pin "6") (pinfunction "FB2MC11_6") (pintype "bidirectional"))
      (node (ref "U1") (pin "60") (pinfunction "(A15)PC7_60") (pintype "bidirectional"))
      (node (ref "U2") (pin "31") (pinfunction "A15_31") (pintype "input"))
    )
    (net (code "37") (name "A16'") (class "Default")
      (node (ref "IC4") (pin "7") (pinfunction "FB2MC12_7") (pintype "bidirectional"))
      (node (ref "U1") (pin "12") (pinfunction "PH0(RXD2)_12") (pintype "bidirectional"))
      (node (ref "U2") (pin "2") (pinfunction "A16_2") (pintype "input"))
    )
    (net (code "38") (name "A17'") (class "Default")
      (node (ref "IC4") (pin "8") (pinfunction "FB2MC14_8") (pintype "bidirectional"))
      (node (ref "U1") (pin "48") (pinfunction "(XCK1)PD5_48") (pintype "bidirectional"))
      (node (ref "U2") (pin "30") (pinfunction "A17_30") (pintype "input"))
    )
    (net (code "39") (name "A18'") (class "Default")
      (node (ref "IC4") (pin "9") (pinfunction "FB2MC15_9") (pintype "bidirectional"))
      (node (ref "U1") (pin "47") (pinfunction "(ICP1)PD4_47") (pintype "bidirectional"))
      (node (ref "U2") (pin "1") (pinfunction "A18_1") (pintype "input"))
    )
    (net (code "40") (name "ALE") (class "Default")
      (node (ref "IC8") (pin "11") (pinfunction "C_11") (pintype "input"))
      (node (ref "U1") (pin "70") (pinfunction "(ALE)PG2_70") (pintype "bidirectional"))
    )
    (net (code "41") (name "AREF") (class "Default")
      (node (ref "C6") (pin "1") (pinfunction "1_1") (pintype "passive"))
      (node (ref "U1") (pin "98") (pinfunction "AREF_98") (pintype "bidirectional"))
    )
    (net (code "42") (name "AUDIO") (class "Default")
      (node (ref "U1") (pin "39") (pinfunction "PL4(OC5B)_39") (pintype "bidirectional"))
    )
    (net (code "43") (name "B0") (class "Default")
      (node (ref "IC9") (pin "12") (pinfunction "8Q_12") (pintype "tri_state"))
      (node (ref "U1") (pin "97") (pinfunction "(ADC0)PF0_97") (pintype "bidirectional"))
    )
    (net (code "44") (name "B1") (class "Default")
      (node (ref "IC9") (pin "13") (pinfunction "7Q_13") (pintype "tri_state"))
      (node (ref "U1") (pin "96") (pinfunction "(ADC1)PF1_96") (pintype "bidirectional"))
    )
    (net (code "45") (name "B2") (class "Default")
      (node (ref "IC9") (pin "14") (pinfunction "6Q_14") (pintype "tri_state"))
      (node (ref "U1") (pin "95") (pinfunction "(ADC2)PF2_95") (pintype "bidirectional"))
    )
    (net (code "46") (name "B3") (class "Default")
      (node (ref "IC9") (pin "15") (pinfunction "5Q_15") (pintype "tri_state"))
      (node (ref "U1") (pin "94") (pinfunction "(ADC3)PF3_94") (pintype "bidirectional"))
    )
    (net (code "47") (name "B4") (class "Default")
      (node (ref "IC9") (pin "16") (pinfunction "4Q_16") (pintype "tri_state"))
      (node (ref "U1") (pin "93") (pinfunction "(ADC4/TCK)PF4_93") (pintype "bidirectional"))
    )
    (net (code "48") (name "B5") (class "Default")
      (node (ref "IC9") (pin "17") (pinfunction "3Q_17") (pintype "tri_state"))
      (node (ref "U1") (pin "92") (pinfunction "(ADC5/TMS)PF5_92") (pintype "bidirectional"))
    )
    (net (code "49") (name "B6") (class "Default")
      (node (ref "IC9") (pin "18") (pinfunction "2Q_18") (pintype "tri_state"))
      (node (ref "U1") (pin "91") (pinfunction "(ADC6/TDO)PF6_91") (pintype "bidirectional"))
    )
    (net (code "50") (name "B7") (class "Default")
      (node (ref "IC9") (pin "19") (pinfunction "1Q_19") (pintype "tri_state"))
      (node (ref "U1") (pin "90") (pinfunction "(ADC7/TDI)PF7_90") (pintype "bidirectional"))
    )
    (net (code "51") (name "CFG_CLK") (class "Default")
      (node (ref "IC4") (pin "54") (pinfunction "FB7MC8_54") (pintype "bidirectional"))
      (node (ref "U1") (pin "79") (pinfunction "PJ7_79") (pintype "bidirectional"))
    )
    (net (code "52") (name "CFG_DATA") (class "Default")
      (node (ref "IC4") (pin "74") (pinfunction "FB6MC2_74") (pintype "bidirectional"))
      (node (ref "U1") (pin "68") (pinfunction "PJ5(PCINT14)_68") (pintype "bidirectional"))
    )
    (net (code "53") (name "CFG_RESET") (class "Default")
      (node (ref "IC4") (pin "59") (pinfunction "FB7MC14_59") (pintype "bidirectional"))
      (node (ref "U1") (pin "69") (pinfunction "PJ6(PCINT15)_69") (pintype "bidirectional"))
    )
    (net (code "54") (name "CS_LLS") (class "Default")
      (node (ref "IC6") (pin "8") (pinfunction "O_8") (pintype "tri_state"))
      (node (ref "MICRO_SD1") (pin "2") (pinfunction "CD/DAT3_2") (pintype "bidirectional"))
    )
    (net (code "55") (name "CTRL_CLK") (class "Default")
      (node (ref "IC3") (pin "9") (pinfunction "I_9") (pintype "input"))
      (node (ref "U1") (pin "64") (pinfunction "PJ1(TXD3/PCINT10)_64") (pintype "bidirectional"))
    )
    (net (code "56") (name "D0") (class "Default")
      (node (ref "4A") (pin "1") (pinfunction "P_1") (pintype "passive"))
      (node (ref "IC4") (pin "18") (pinfunction "FB1MC12_18") (pintype "bidirectional"))
      (node (ref "IC5") (pin "12") (pinfunction "8Q_12") (pintype "tri_state"))
      (node (ref "IC8") (pin "9") (pinfunction "8D_9") (pintype "input"))
      (node (ref "IC9") (pin "9") (pinfunction "8D_9") (pintype "input"))
      (node (ref "U1") (pin "78") (pinfunction "(AD0)PA0_78") (pintype "bidirectional"))
      (node (ref "U2") (pin "13") (pinfunction "DQ0_13") (pintype "output"))
    )
    (net (code "57") (name "D1") (class "Default")
      (node (ref "5A") (pin "1") (pinfunction "P_1") (pintype "passive"))
      (node (ref "IC4") (pin "19") (pinfunction "FB1MC14_19") (pintype "bidirectional"))
      (node (ref "IC5") (pin "13") (pinfunction "7Q_13") (pintype "tri_state"))
      (node (ref "IC8") (pin "8") (pinfunction "7D_8") (pintype "input"))
      (node (ref "IC9") (pin "8") (pinfunction "7D_8") (pintype "input"))
      (node (ref "U1") (pin "77") (pinfunction "(AD1)PA1_77") (pintype "bidirectional"))
      (node (ref "U2") (pin "14") (pinfunction "DQ1_14") (pintype "output"))
    )
    (net (code "58") (name "D2") (class "Default")
      (node (ref "6A") (pin "1") (pinfunction "P_1") (pintype "passive"))
      (node (ref "IC4") (pin "20") (pinfunction "FB1MC15_20") (pintype "bidirectional"))
      (node (ref "IC5") (pin "14") (pinfunction "6Q_14") (pintype "tri_state"))
      (node (ref "IC8") (pin "7") (pinfunction "6D_7") (pintype "input"))
      (node (ref "IC9") (pin "7") (pinfunction "6D_7") (pintype "input"))
      (node (ref "U1") (pin "76") (pinfunction "(AD2)PA2_76") (pintype "bidirectional"))
      (node (ref "U2") (pin "15") (pinfunction "DQ2_15") (pintype "output"))
    )
    (net (code "59") (name "D3") (class "Default")
      (node (ref "9A") (pin "1") (pinfunction "P_1") (pintype "passive"))
      (node (ref "IC4") (pin "29") (pinfunction "FB3MC11_29") (pintype "bidirectional"))
      (node (ref "IC5") (pin "15") (pinfunction "5Q_15") (pintype "tri_state"))
      (node (ref "IC8") (pin "6") (pinfunction "5D_6") (pintype "input"))
      (node (ref "IC9") (pin "6") (pinfunction "5D_6") (pintype "input"))
      (node (ref "U1") (pin "75") (pinfunction "(AD3)PA3_75") (pintype "bidirectional"))
      (node (ref "U2") (pin "17") (pinfunction "DQ3_17") (pintype "output"))
    )
    (net (code "60") (name "D4") (class "Default")
      (node (ref "10A") (pin "1") (pinfunction "P_1") (pintype "passive"))
      (node (ref "IC4") (pin "32") (pinfunction "FB3MC14_32") (pintype "bidirectional"))
      (node (ref "IC5") (pin "16") (pinfunction "4Q_16") (pintype "tri_state"))
      (node (ref "IC8") (pin "5") (pinfunction "4D_5") (pintype "input"))
      (node (ref "IC9") (pin "5") (pinfunction "4D_5") (pintype "input"))
      (node (ref "U1") (pin "74") (pinfunction "(AD4)PA4_74") (pintype "bidirectional"))
      (node (ref "U2") (pin "18") (pinfunction "DQ4_18") (pintype "output"))
    )
    (net (code "61") (name "D5") (class "Default")
      (node (ref "8A") (pin "1") (pinfunction "P_1") (pintype "passive"))
      (node (ref "IC4") (pin "25") (pinfunction "FB3MC6_25") (pintype "bidirectional"))
      (node (ref "IC5") (pin "17") (pinfunction "3Q_17") (pintype "tri_state"))
      (node (ref "IC8") (pin "4") (pinfunction "3D_4") (pintype "input"))
      (node (ref "IC9") (pin "4") (pinfunction "3D_4") (pintype "input"))
      (node (ref "U1") (pin "73") (pinfunction "(AD5)PA5_73") (pintype "bidirectional"))
      (node (ref "U2") (pin "19") (pinfunction "DQ5_19") (pintype "output"))
    )
    (net (code "62") (name "D6") (class "Default")
      (node (ref "7A") (pin "1") (pinfunction "P_1") (pintype "passive"))
      (node (ref "IC4") (pin "23") (pinfunction "GCK2_23") (pintype "bidirectional"))
      (node (ref "IC5") (pin "18") (pinfunction "2Q_18") (pintype "tri_state"))
      (node (ref "IC8") (pin "3") (pinfunction "2D_3") (pintype "input"))
      (node (ref "IC9") (pin "3") (pinfunction "2D_3") (pintype "input"))
      (node (ref "U1") (pin "72") (pinfunction "(AD6)PA6_72") (pintype "bidirectional"))
      (node (ref "U2") (pin "20") (pinfunction "DQ6_20") (pintype "output"))
    )
    (net (code "63") (name "D7") (class "Default")
      (node (ref "1A") (pin "1") (pinfunction "P_1") (pintype "passive"))
      (node (ref "IC3") (pin "8") (pinfunction "O_8") (pintype "tri_state"))
      (node (ref "IC4") (pin "16") (pinfunction "FB1MC9_16") (pintype "bidirectional"))
      (node (ref "IC5") (pin "19") (pinfunction "1Q_19") (pintype "tri_state"))
      (node (ref "IC8") (pin "2") (pinfunction "1D_2") (pintype "input"))
      (node (ref "IC9") (pin "2") (pinfunction "1D_2") (pintype "input"))
      (node (ref "U1") (pin "71") (pinfunction "(AD7)PA7_71") (pintype "bidirectional"))
      (node (ref "U2") (pin "21") (pinfunction "DQ7_21") (pintype "output"))
    )
    (net (code "64") (name "DI_LLS") (class "Default")
      (node (ref "IC6") (pin "3") (pinfunction "O_3") (pintype "tri_state"))
      (node (ref "MICRO_SD1") (pin "3") (pinfunction "CMD_3") (pintype "bidirectional"))
    )
    (net (code "65") (name "DOWN") (class "Default")
      (node (ref "IC4") (pin "66") (pinfunction "FB8MC8_66") (pintype "bidirectional"))
      (node (ref "J2") (pin "2") (pinfunction "2_2") (pintype "passive"))
    )
    (net (code "66") (name "DO_LLC") (class "Default")
      (node (ref "IC6") (pin "12") (pinfunction "I_12") (pintype "input"))
      (node (ref "R20") (pin "1") (pinfunction "1_1") (pintype "passive"))
    )
    (net (code "67") (name "EN_M1_NOT") (class "Default")
      (node (ref "IC4") (pin "76") (pinfunction "FB6MC5_76") (pintype "bidirectional"))
      (node (ref "U1") (pin "40") (pinfunction "PL5(OC5C)_40") (pintype "bidirectional"))
    )
    (net (code "68") (name "FIRE") (class "Default")
      (node (ref "IC4") (pin "70") (pinfunction "FB8MC12_70") (pintype "bidirectional"))
      (node (ref "J2") (pin "6") (pinfunction "6_6") (pintype "passive"))
    )
    (net (code "69") (name "GET_CTRL_REG") (class "Default")
      (node (ref "IC4") (pin "86") (pinfunction "FB6MC17_86") (pintype "bidirectional"))
      (node (ref "U1") (pin "46") (pinfunction "(TXD1/INT3)PD3_46") (pintype "bidirectional"))
    )
    (net (code "70") (name "GET_DATA_REG") (class "Default")
      (node (ref "IC4") (pin "85") (pinfunction "FB6MC15_85") (pintype "bidirectional"))
      (node (ref "U1") (pin "45") (pinfunction "(RXD1/INT2)PD2_45") (pintype "bidirectional"))
    )
    (net (code "71") (name "GND") (class "Default")
      (node (ref "4B") (pin "1") (pinfunction "P_1") (pintype "passive"))
      (node (ref "5B") (pin "1") (pinfunction "P_1") (pintype "passive"))
      (node (ref "C1") (pin "2") (pinfunction "2_2") (pintype "passive"))
      (node (ref "C13") (pin "2") (pinfunction "2_2") (pintype "passive"))
      (node (ref "C14") (pin "2") (pinfunction "2_2") (pintype "passive"))
      (node (ref "C15") (pin "2") (pinfunction "2_2") (pintype "passive"))
      (node (ref "C16") (pin "1") (pinfunction "1_1") (pintype "passive"))
      (node (ref "C17") (pin "1") (pinfunction "1_1") (pintype "passive"))
      (node (ref "C18") (pin "2") (pinfunction "2_2") (pintype "passive"))
      (node (ref "C19") (pin "2") (pinfunction "2_2") (pintype "passive"))
      (node (ref "C2") (pin "2") (pinfunction "2_2") (pintype "passive"))
      (node (ref "C20") (pin "1") (pinfunction "1_1") (pintype "passive"))
      (node (ref "C21") (pin "1") (pinfunction "1_1") (pintype "passive"))
      (node (ref "C3") (pin "2") (pinfunction "2_2") (pintype "passive"))
      (node (ref "C5") (pin "1") (pinfunction "1_1") (pintype "passive"))
      (node (ref "C6") (pin "2") (pinfunction "2_2") (pintype "passive"))
      (node (ref "C8") (pin "1") (pinfunction "1_1") (pintype "passive"))
      (node (ref "IC1") (pin "3") (pinfunction "GND_3") (pintype "passive"))
      (node (ref "IC10") (pin "2") (pinfunction "VSS_2") (pintype "passive"))
      (node (ref "IC10") (pin "6") (pinfunction "A0_6") (pintype "passive"))
      (node (ref "IC2") (pin "1") (pinfunction "GND_1") (pintype "power_in"))
      (node (ref "IC4") (pin "100") (pinfunction "GND8_100") (pintype "power_in"))
      (node (ref "IC4") (pin "21") (pinfunction "GND1_21") (pintype "power_in"))
      (node (ref "IC4") (pin "31") (pinfunction "GND2_31") (pintype "power_in"))
      (node (ref "IC4") (pin "44") (pinfunction "GND3_44") (pintype "power_in"))
      (node (ref "IC4") (pin "62") (pinfunction "GND4_62") (pintype "power_in"))
      (node (ref "IC4") (pin "69") (pinfunction "GND5_69") (pintype "power_in"))
      (node (ref "IC4") (pin "75") (pinfunction "GND6_75") (pintype "power_in"))
      (node (ref "IC4") (pin "84") (pinfunction "GND7_84") (pintype "power_in"))
      (node (ref "IC6") (pin "1") (pinfunction "OE_1") (pintype "input"))
      (node (ref "IC6") (pin "10") (pinfunction "OE_10") (pintype "input"))
      (node (ref "IC6") (pin "13") (pinfunction "OE_13") (pintype "input"))
      (node (ref "IC6") (pin "4") (pinfunction "OE_4") (pintype "input"))
      (node (ref "IC6") (pin "7") (pinfunction "GND_7") (pintype "power_in"))
      (node (ref "IC7") (pin "1") (pinfunction "GND_1") (pintype "bidirectional"))
      (node (ref "J1") (pin "5") (pinfunction "GND_5") (pintype "power_in"))
      (node (ref "J1") (pin "S1") (pinfunction "SHIELD_S1") (pintype "passive"))
      (node (ref "J1") (pin "S2") (pinfunction "SHIELD_S2") (pintype "passive"))
      (node (ref "J1") (pin "S3") (pinfunction "SHIELD_S3") (pintype "passive"))
      (node (ref "J1") (pin "S4") (pinfunction "SHIELD_S4") (pintype "passive"))
      (node (ref "J1") (pin "S5") (pinfunction "SHIELD_S5") (pintype "passive"))
      (node (ref "J1") (pin "S6") (pinfunction "SHIELD_S6") (pintype "passive"))
      (node (ref "J2") (pin "8") (pinfunction "8_8") (pintype "passive"))
      (node (ref "JP1") (pin "1") (pinfunction "1_1") (pintype "passive"))
      (node (ref "JP2") (pin "2") (pinfunction "2_2") (pintype "passive"))
      (node (ref "JP6") (pin "6") (pinfunction "6_6") (pintype "passive"))
      (node (ref "LED3") (pin "P1") (pinfunction "C_P1") (pintype "passive"))
      (node (ref "LED3") (pin "P2") (pinfunction "C_P2") (pintype "passive"))
      (node (ref "LED3") (pin "P3") (pinfunction "C_P3") (pintype "passive"))
      (node (ref "MICRO_SD1") (pin "6") (pinfunction "VSS_6") (pintype "power_in"))
      (node (ref "MICRO_SD1") (pin "MP1") (pinfunction "SHIELD_MP1") (pintype "power_in"))
      (node (ref "MICRO_SD1") (pin "MP2") (pinfunction "SHIELD_MP2") (pintype "power_in"))
      (node (ref "MICRO_SD1") (pin "MP3") (pinfunction "SHIELD_MP3") (pintype "power_in"))
      (node (ref "MICRO_SD1") (pin "MP4") (pinfunction "SHIELD_MP4") (pintype "power_in"))
      (node (ref "R10") (pin "1") (pinfunction "1_1") (pintype "passive"))
      (node (ref "R26") (pin "2") (pinfunction "2_2") (pintype "passive"))
      (node (ref "R8") (pin "1") (pinfunction "1_1") (pintype "passive"))
      (node (ref "R9") (pin "1") (pinfunction "1_1") (pintype "passive"))
      (node (ref "S1") (pin "1") (pinfunction "P_1") (pintype "passive"))
      (node (ref "U1") (pin "11") (pinfunction "GND_11") (pintype "power_in"))
      (node (ref "U1") (pin "32") (pinfunction "GND1_32") (pintype "power_in"))
      (node (ref "U1") (pin "62") (pinfunction "GND2_62") (pintype "power_in"))
      (node (ref "U1") (pin "81") (pinfunction "GND3_81") (pintype "power_in"))
      (node (ref "U1") (pin "99") (pinfunction "AGND_99") (pintype "power_in"))
      (node (ref "U2") (pin "16") (pinfunction "VSS_16") (pintype "output"))
    )
    (net (code "72") (name "LEDB") (class "Default")
      (node (ref "R3") (pin "1") (pinfunction "1_1") (pintype "passive"))
      (node (ref "U1") (pin "7") (pinfunction "(OC3C/INT5)PE5_7") (pintype "bidirectional"))
    )
    (net (code "73") (name "LEDG") (class "Default")
      (node (ref "R13") (pin "1") (pinfunction "1_1") (pintype "passive"))
      (node (ref "U1") (pin "1") (pinfunction "(OC0B)PG5_1") (pintype "bidirectional"))
    )
    (net (code "74") (name "LEDR") (class "Default")
      (node (ref "R2") (pin "1") (pinfunction "1_1") (pintype "passive"))
      (node (ref "U1") (pin "6") (pinfunction "(OC3B/INT4)PE4_6") (pintype "bidirectional"))
    )
    (net (code "75") (name "LEFT") (class "Default")
      (node (ref "IC4") (pin "67") (pinfunction "FB8MC9_67") (pintype "bidirectional"))
      (node (ref "J2") (pin "3") (pinfunction "3_3") (pintype "passive"))
    )
    (net (code "76") (name "LE_IL") (class "Default")
      (node (ref "IC5") (pin "11") (pinfunction "C_11") (pintype "input"))
      (node (ref "U1") (pin "5") (pinfunction "(OC3A/AIN1)PE3_5") (pintype "bidirectional"))
    )
    (net (code "77") (name "LE_OL") (class "Default")
      (node (ref "IC4") (pin "72") (pinfunction "FB8MC15_72") (pintype "bidirectional"))
      (node (ref "IC9") (pin "11") (pinfunction "C_11") (pintype "input"))
    )
    (net (code "78") (name "MISO") (class "Default")
      (node (ref "JP6") (pin "1") (pinfunction "1_1") (pintype "passive"))
      (node (ref "R1") (pin "1") (pinfunction "1_1") (pintype "passive"))
      (node (ref "U1") (pin "22") (pinfunction "(MISO/PCINT3)PB3_22") (pintype "bidirectional"))
    )
    (net (code "79") (name "MOSI") (class "Default")
      (node (ref "JP6") (pin "4") (pinfunction "4_4") (pintype "passive"))
      (node (ref "R17") (pin "1") (pinfunction "1_1") (pintype "passive"))
      (node (ref "U1") (pin "21") (pinfunction "(MOSI/PCINT2)PB2_21") (pintype "bidirectional"))
    )
    (net (code "80") (name "Net-(IC4-FB5MC8)") (class "Default")
      (node (ref "IC4") (pin "39") (pinfunction "FB5MC8_39") (pintype "bidirectional"))
      (node (ref "SJ2") (pin "1") (pinfunction "1_1") (pintype "passive"))
    )
    (net (code "81") (name "Net-(IC4-FB8MC17)") (class "Default")
      (node (ref "IC4") (pin "73") (pinfunction "FB8MC17_73") (pintype "bidirectional"))
      (node (ref "PAD6") (pin "1") (pinfunction "P_1") (pintype "passive"))
    )
    (net (code "82") (name "Net-(IC4-GCK3)") (class "Default")
      (node (ref "IC4") (pin "27") (pinfunction "GCK3_27") (pintype "bidirectional"))
      (node (ref "PAD1") (pin "1") (pinfunction "P_1") (pintype "passive"))
    )
    (net (code "83") (name "Net-(IC6A-I)") (class "Default")
      (node (ref "IC6") (pin "2") (pinfunction "I_2") (pintype "input"))
      (node (ref "R17") (pin "2") (pinfunction "2_2") (pintype "passive"))
    )
    (net (code "84") (name "Net-(IC6B-I)") (class "Default")
      (node (ref "IC6") (pin "5") (pinfunction "I_5") (pintype "input"))
      (node (ref "R18") (pin "2") (pinfunction "2_2") (pintype "passive"))
    )
    (net (code "85") (name "Net-(IC6C-I)") (class "Default")
      (node (ref "IC6") (pin "9") (pinfunction "I_9") (pintype "input"))
      (node (ref "R21") (pin "2") (pinfunction "2_2") (pintype "passive"))
    )
    (net (code "86") (name "Net-(IC6D-O)") (class "Default")
      (node (ref "IC6") (pin "11") (pinfunction "O_11") (pintype "tri_state"))
      (node (ref "R1") (pin "2") (pinfunction "2_2") (pintype "passive"))
    )
    (net (code "87") (name "Net-(IC7-DTR)") (class "Default")
      (node (ref "C9") (pin "2") (pinfunction "2_2") (pintype "passive"))
      (node (ref "IC7") (pin "13") (pinfunction "DTR_13") (pintype "bidirectional"))
      (node (ref "R26") (pin "1") (pinfunction "1_1") (pintype "passive"))
    )
    (net (code "88") (name "Net-(IC7-RX)") (class "Default")
      (node (ref "IC7") (pin "3") (pinfunction "RX_3") (pintype "bidirectional"))
      (node (ref "R23") (pin "2") (pinfunction "2_2") (pintype "passive"))
    )
    (net (code "89") (name "Net-(IC7-TX)") (class "Default")
      (node (ref "IC7") (pin "2") (pinfunction "TX_2") (pintype "bidirectional"))
      (node (ref "R22") (pin "2") (pinfunction "2_2") (pintype "passive"))
    )
    (net (code "90") (name "Net-(IC7-V3)") (class "Default")
      (node (ref "C8") (pin "2") (pinfunction "2_2") (pintype "passive"))
      (node (ref "IC7") (pin "4") (pinfunction "V3_4") (pintype "bidirectional"))
    )
    (net (code "91") (name "Net-(IC7-XI)") (class "Default")
      (node (ref "C20") (pin "2") (pinfunction "2_2") (pintype "passive"))
      (node (ref "IC7") (pin "7") (pinfunction "XI_7") (pintype "bidirectional"))
      (node (ref "Q2") (pin "3") (pinfunction "2_3") (pintype "passive"))
      (node (ref "R27") (pin "2") (pinfunction "2_2") (pintype "passive"))
    )
    (net (code "92") (name "Net-(IC7-XO)") (class "Default")
      (node (ref "C21") (pin "2") (pinfunction "2_2") (pintype "passive"))
      (node (ref "IC7") (pin "8") (pinfunction "XO_8") (pintype "bidirectional"))
      (node (ref "Q2") (pin "1") (pinfunction "1_1") (pintype "passive"))
      (node (ref "R27") (pin "1") (pinfunction "1_1") (pintype "passive"))
    )
    (net (code "93") (name "Net-(J1-D+)") (class "Default")
      (node (ref "J1") (pin "3") (pinfunction "D+_3") (pintype "bidirectional"))
      (node (ref "R29") (pin "2") (pinfunction "2_2") (pintype "passive"))
    )
    (net (code "94") (name "Net-(J1-D-)") (class "Default")
      (node (ref "J1") (pin "2") (pinfunction "D-_2") (pintype "bidirectional"))
      (node (ref "R28") (pin "2") (pinfunction "2_2") (pintype "passive"))
    )
    (net (code "95") (name "Net-(LED2-PadA)") (class "Default")
      (node (ref "LED2") (pin "A") (pinfunction "A_A") (pintype "passive"))
      (node (ref "R11") (pin "2") (pinfunction "2_2") (pintype "passive"))
    )
    (net (code "96") (name "Net-(LED3A-A)") (class "Default")
      (node (ref "LED3") (pin "P6") (pinfunction "A_P6") (pintype "passive"))
      (node (ref "R3") (pin "2") (pinfunction "2_2") (pintype "passive"))
    )
    (net (code "97") (name "Net-(LED3B-A)") (class "Default")
      (node (ref "LED3") (pin "P5") (pinfunction "A_P5") (pintype "passive"))
      (node (ref "R13") (pin "2") (pinfunction "2_2") (pintype "passive"))
    )
    (net (code "98") (name "Net-(LED3C-A)") (class "Default")
      (node (ref "LED3") (pin "P4") (pinfunction "A_P4") (pintype "passive"))
      (node (ref "R2") (pin "2") (pinfunction "2_2") (pintype "passive"))
    )
    (net (code "99") (name "Net-(MICRO_SD1-DAT0)") (class "Default")
      (node (ref "MICRO_SD1") (pin "7") (pinfunction "DAT0_7") (pintype "bidirectional"))
      (node (ref "R20") (pin "2") (pinfunction "2_2") (pintype "passive"))
    )
    (net (code "100") (name "Net-(PAD2-P)") (class "Default")
      (node (ref "PAD2") (pin "1") (pinfunction "P_1") (pintype "passive"))
      (node (ref "U1") (pin "27") (pinfunction "PH7(T4)_27") (pintype "bidirectional"))
    )
    (net (code "101") (name "Net-(PAD3-P)") (class "Default")
      (node (ref "PAD3") (pin "1") (pinfunction "P_1") (pintype "passive"))
      (node (ref "U1") (pin "28") (pinfunction "(TOSC2)PG3_28") (pintype "bidirectional"))
    )
    (net (code "102") (name "Net-(Q1-2)") (class "Default")
      (node (ref "C16") (pin "2") (pinfunction "2_2") (pintype "passive"))
      (node (ref "Q1") (pin "3") (pinfunction "2_3") (pintype "passive"))
      (node (ref "R19") (pin "2") (pinfunction "2_2") (pintype "passive"))
      (node (ref "U1") (pin "33") (pinfunction "XTAL2_33") (pintype "output"))
    )
    (net (code "103") (name "Net-(U1-XTAL1)") (class "Default")
      (node (ref "C17") (pin "2") (pinfunction "2_2") (pintype "passive"))
      (node (ref "Q1") (pin "1") (pinfunction "1_1") (pintype "passive"))
      (node (ref "R19") (pin "1") (pinfunction "1_1") (pintype "passive"))
      (node (ref "U1") (pin "34") (pinfunction "XTAL1_34") (pintype "input"))
    )
    (net (code "104") (name "O0") (class "Default")
      (node (ref "IC5") (pin "9") (pinfunction "8D_9") (pintype "input"))
      (node (ref "U1") (pin "89") (pinfunction "PK0(ADC8/PCINT16)_89") (pintype "bidirectional"))
    )
    (net (code "105") (name "O1") (class "Default")
      (node (ref "IC5") (pin "8") (pinfunction "7D_8") (pintype "input"))
      (node (ref "U1") (pin "88") (pinfunction "PK1(ADC9/PCINT17)_88") (pintype "bidirectional"))
    )
    (net (code "106") (name "O2") (class "Default")
      (node (ref "IC5") (pin "7") (pinfunction "6D_7") (pintype "input"))
      (node (ref "U1") (pin "87") (pinfunction "PK2(ADC10/PCINT18)_87") (pintype "bidirectional"))
    )
    (net (code "107") (name "O3") (class "Default")
      (node (ref "IC5") (pin "6") (pinfunction "5D_6") (pintype "input"))
      (node (ref "U1") (pin "86") (pinfunction "PK3(ADC11/PCINT19)_86") (pintype "bidirectional"))
    )
    (net (code "108") (name "O4") (class "Default")
      (node (ref "IC5") (pin "5") (pinfunction "4D_5") (pintype "input"))
      (node (ref "U1") (pin "85") (pinfunction "PK4(ADC12/PCINT20)_85") (pintype "bidirectional"))
    )
    (net (code "109") (name "O5") (class "Default")
      (node (ref "IC5") (pin "4") (pinfunction "3D_4") (pintype "input"))
      (node (ref "U1") (pin "84") (pinfunction "PK5(ADC13/PCINT21)_84") (pintype "bidirectional"))
    )
    (net (code "110") (name "O6") (class "Default")
      (node (ref "IC5") (pin "3") (pinfunction "2D_3") (pintype "input"))
      (node (ref "U1") (pin "83") (pinfunction "PK6(ADC14/PCINT22)_83") (pintype "bidirectional"))
    )
    (net (code "111") (name "O7") (class "Default")
      (node (ref "IC5") (pin "2") (pinfunction "1D_2") (pintype "input"))
      (node (ref "U1") (pin "82") (pinfunction "PK7(ADC15/PCINT23)_82") (pintype "bidirectional"))
    )
    (net (code "112") (name "OE_OL") (class "Default")
      (node (ref "IC9") (pin "1") (pinfunction "OC_1") (pintype "input"))
      (node (ref "U1") (pin "13") (pinfunction "PH1(TXD2)_13") (pintype "bidirectional"))
    )
    (net (code "113") (name "PAGE_A8") (class "Default")
      (node (ref "IC4") (pin "80") (pinfunction "FB6MC11_80") (pintype "bidirectional"))
      (node (ref "U1") (pin "41") (pinfunction "PL6_41") (pintype "bidirectional"))
    )
    (net (code "114") (name "RD+") (class "Default")
      (node (ref "IC7") (pin "5") (pinfunction "D+_5") (pintype "bidirectional"))
      (node (ref "R29") (pin "1") (pinfunction "1_1") (pintype "passive"))
    )
    (net (code "115") (name "RD-") (class "Default")
      (node (ref "IC7") (pin "6") (pinfunction "D-_6") (pintype "bidirectional"))
      (node (ref "R28") (pin "1") (pinfunction "1_1") (pintype "passive"))
    )
    (net (code "116") (name "RESET") (class "Default")
      (node (ref "C5") (pin "2") (pinfunction "2_2") (pintype "passive"))
      (node (ref "C9") (pin "1") (pinfunction "1_1") (pintype "passive"))
      (node (ref "D1") (pin "A") (pinfunction "A_A") (pintype "passive"))
      (node (ref "JP6") (pin "5") (pinfunction "5_5") (pintype "passive"))
      (node (ref "R15") (pin "1") (pinfunction "1_1") (pintype "passive"))
      (node (ref "S1") (pin "2") (pinfunction "S_2") (pintype "passive"))
      (node (ref "U1") (pin "30") (pinfunction "RESET_30") (pintype "input"))
    )
    (net (code "117") (name "RIGHT") (class "Default")
      (node (ref "IC4") (pin "68") (pinfunction "FB8MC11_68") (pintype "bidirectional"))
      (node (ref "J2") (pin "4") (pinfunction "4_4") (pintype "passive"))
    )
    (net (code "118") (name "ROM_WR_EN") (class "Default")
      (node (ref "IC4") (pin "79") (pinfunction "FB6MC9_79") (pintype "bidirectional"))
      (node (ref "U1") (pin "36") (pinfunction "PL1(ICP5)_36") (pintype "bidirectional"))
    )
    (net (code "119") (name "RST_CTRL_REG") (class "Default")
      (node (ref "IC4") (pin "82") (pinfunction "FB6MC14_82") (pintype "bidirectional"))
      (node (ref "U1") (pin "26") (pinfunction "(OC0A/OC1C/PCINT7)PB7_26") (pintype "bidirectional"))
    )
    (net (code "120") (name "RST_DATA_REG") (class "Default")
      (node (ref "IC4") (pin "81") (pinfunction "FB6MC12_81") (pintype "bidirectional"))
      (node (ref "U1") (pin "63") (pinfunction "PJ0(RXD3/PCINT9)_63") (pintype "bidirectional"))
    )
    (net (code "121") (name "RX0") (class "Default")
      (node (ref "R23") (pin "1") (pinfunction "1_1") (pintype "passive"))
      (node (ref "U1") (pin "3") (pinfunction "(TXD0)PE1_3") (pintype "bidirectional"))
    )
    (net (code "122") (name "SCK_LLS") (class "Default")
      (node (ref "IC6") (pin "6") (pinfunction "O_6") (pintype "tri_state"))
      (node (ref "MICRO_SD1") (pin "5") (pinfunction "CLK_5") (pintype "bidirectional"))
    )
    (net (code "123") (name "SCL") (class "Default")
      (node (ref "IC10") (pin "5") (pinfunction "SCL_5") (pintype "passive"))
      (node (ref "U1") (pin "43") (pinfunction "(SCL/INT0)PD0_43") (pintype "bidirectional"))
    )
    (net (code "124") (name "SCLK") (class "Default")
      (node (ref "JP6") (pin "3") (pinfunction "3_3") (pintype "passive"))
      (node (ref "R18") (pin "1") (pinfunction "1_1") (pintype "passive"))
      (node (ref "U1") (pin "20") (pinfunction "(SCK/PCINT1)PB1_20") (pintype "bidirectional"))
    )
    (net (code "125") (name "SDA") (class "Default")
      (node (ref "IC10") (pin "4") (pinfunction "SDA_4") (pintype "passive"))
      (node (ref "U1") (pin "44") (pinfunction "(SDA/INT1)PD1_44") (pintype "bidirectional"))
    )
    (net (code "126") (name "SD_LED") (class "Default")
      (node (ref "LED2") (pin "C") (pinfunction "C_C") (pintype "passive"))
      (node (ref "U1") (pin "37") (pinfunction "PL2(T5)_37") (pintype "bidirectional"))
    )
    (net (code "127") (name "SEL_128CHARS") (class "Default")
      (node (ref "IC4") (pin "78") (pinfunction "FB6MC8_78") (pintype "bidirectional"))
      (node (ref "U1") (pin "35") (pinfunction "PL0(ICP4)_35") (pintype "bidirectional"))
    )
    (net (code "128") (name "SPARE1") (class "Default")
      (node (ref "IC4") (pin "77") (pinfunction "FB6MC6_77") (pintype "bidirectional"))
      (node (ref "U1") (pin "38") (pinfunction "PL3(OC5A)_38") (pintype "bidirectional"))
    )
    (net (code "129") (name "SPEAKER") (class "Default")
      (node (ref "IC10") (pin "1") (pinfunction "VOUT_1") (pintype "passive"))
      (node (ref "JP1") (pin "2") (pinfunction "2_2") (pintype "passive"))
    )
    (net (code "130") (name "SS_SD") (class "Default")
      (node (ref "R21") (pin "1") (pinfunction "1_1") (pintype "passive"))
      (node (ref "U1") (pin "19") (pinfunction "(SS/PCINT0)PB0_19") (pintype "bidirectional"))
    )
    (net (code "131") (name "TCK") (class "Default")
      (node (ref "IC4") (pin "48") (pinfunction "TCK_48") (pintype "passive"))
      (node (ref "JP3") (pin "1") (pinfunction "1_1") (pintype "passive"))
      (node (ref "R7") (pin "2") (pinfunction "2_2") (pintype "passive"))
      (node (ref "R8") (pin "2") (pinfunction "2_2") (pintype "passive"))
    )
    (net (code "132") (name "TCK'") (class "Default")
      (node (ref "R7") (pin "1") (pinfunction "1_1") (pintype "passive"))
      (node (ref "U1") (pin "24") (pinfunction "(OC1A/PCINT5)PB5_24") (pintype "bidirectional"))
    )
    (net (code "133") (name "TDI") (class "Default")
      (node (ref "IC4") (pin "45") (pinfunction "TDI_45") (pintype "passive"))
      (node (ref "JP3") (pin "3") (pinfunction "3_3") (pintype "passive"))
      (node (ref "R5") (pin "2") (pinfunction "2_2") (pintype "passive"))
      (node (ref "R9") (pin "2") (pinfunction "2_2") (pintype "passive"))
    )
    (net (code "134") (name "TDI'") (class "Default")
      (node (ref "R5") (pin "1") (pinfunction "1_1") (pintype "passive"))
      (node (ref "U1") (pin "18") (pinfunction "PH6(OC2B)_18") (pintype "bidirectional"))
    )
    (net (code "135") (name "TDO") (class "Default")
      (node (ref "IC4") (pin "83") (pinfunction "TDO_83") (pintype "passive"))
      (node (ref "JP3") (pin "2") (pinfunction "2_2") (pintype "passive"))
      (node (ref "R6") (pin "2") (pinfunction "2_2") (pintype "passive"))
    )
    (net (code "136") (name "TDO'") (class "Default")
      (node (ref "R6") (pin "1") (pinfunction "1_1") (pintype "passive"))
      (node (ref "U1") (pin "17") (pinfunction "PH5(OC4C)_17") (pintype "bidirectional"))
    )
    (net (code "137") (name "TMS") (class "Default")
      (node (ref "IC4") (pin "47") (pinfunction "TMS_47") (pintype "passive"))
      (node (ref "JP3") (pin "4") (pinfunction "4_4") (pintype "passive"))
      (node (ref "R10") (pin "2") (pinfunction "2_2") (pintype "passive"))
      (node (ref "R4") (pin "2") (pinfunction "2_2") (pintype "passive"))
    )
    (net (code "138") (name "TMS'") (class "Default")
      (node (ref "R4") (pin "1") (pinfunction "1_1") (pintype "passive"))
      (node (ref "U1") (pin "23") (pinfunction "(OC2A/PCINT4)PB4_23") (pintype "bidirectional"))
    )
    (net (code "139") (name "TX0") (class "Default")
      (node (ref "R22") (pin "1") (pinfunction "1_1") (pintype "passive"))
      (node (ref "U1") (pin "2") (pinfunction "(RXD0/PCIN8)PE0_2") (pintype "bidirectional"))
    )
    (net (code "140") (name "UP") (class "Default")
      (node (ref "IC4") (pin "65") (pinfunction "FB8MC6_65") (pintype "bidirectional"))
      (node (ref "J2") (pin "1") (pinfunction "1_1") (pintype "passive"))
    )
    (net (code "141") (name "VCC") (class "Default")
      (node (ref "C1") (pin "1") (pinfunction "1_1") (pintype "passive"))
      (node (ref "C13") (pin "1") (pinfunction "1_1") (pintype "passive"))
      (node (ref "C14") (pin "1") (pinfunction "1_1") (pintype "passive"))
      (node (ref "C15") (pin "1") (pinfunction "1_1") (pintype "passive"))
      (node (ref "C19") (pin "1") (pinfunction "1_1") (pintype "passive"))
      (node (ref "C2") (pin "1") (pinfunction "1_1") (pintype "passive"))
      (node (ref "C3") (pin "1") (pinfunction "1_1") (pintype "passive"))
      (node (ref "D1") (pin "C") (pinfunction "C_C") (pintype "passive"))
      (node (ref "IC1") (pin "2") (pinfunction "VO_2") (pintype "passive"))
      (node (ref "IC10") (pin "3") (pinfunction "VDD_3") (pintype "passive"))
      (node (ref "IC2") (pin "3") (pinfunction "VIN_3") (pintype "input"))
      (node (ref "IC3") (pin "12") (pinfunction "I_12") (pintype "input"))
      (node (ref "IC3") (pin "13") (pinfunction "OE_13") (pintype "input"))
      (node (ref "IC3") (pin "2") (pinfunction "I_2") (pintype "input"))
      (node (ref "IC3") (pin "5") (pinfunction "I_5") (pintype "input"))
      (node (ref "IC7") (pin "16") (pinfunction "VCC_16") (pintype "bidirectional"))
      (node (ref "J1") (pin "1") (pinfunction "VBUS_1") (pintype "power_in"))
      (node (ref "JP6") (pin "2") (pinfunction "2_2") (pintype "passive"))
      (node (ref "R11") (pin "1") (pinfunction "1_1") (pintype "passive"))
      (node (ref "R15") (pin "2") (pinfunction "2_2") (pintype "passive"))
      (node (ref "SJ1") (pin "2") (pinfunction "2_2") (pintype "passive"))
      (node (ref "U1") (pin "10") (pinfunction "VCC_10") (pintype "power_in"))
      (node (ref "U1") (pin "100") (pinfunction "AVCC_100") (pintype "power_in"))
      (node (ref "U1") (pin "31") (pinfunction "VCC1_31") (pintype "power_in"))
      (node (ref "U1") (pin "61") (pinfunction "VCC2_61") (pintype "power_in"))
      (node (ref "U1") (pin "80") (pinfunction "VCC3_80") (pintype "power_in"))
      (node (ref "U2") (pin "32") (pinfunction "VCC_32") (pintype "power_in"))
    )
    (net (code "142") (name "unconnected-(IC3D-O-Pad11)") (class "Default")
      (node (ref "IC3") (pin "11") (pinfunction "O_11") (pintype "tri_state"))
    )
    (net (code "143") (name "unconnected-(IC7-CTS-Pad9)") (class "Default")
      (node (ref "IC7") (pin "9") (pinfunction "CTS_9") (pintype "bidirectional"))
    )
    (net (code "144") (name "unconnected-(IC7-DCD-Pad12)") (class "Default")
      (node (ref "IC7") (pin "12") (pinfunction "DCD_12") (pintype "bidirectional"))
    )
    (net (code "145") (name "unconnected-(IC7-DSR-Pad10)") (class "Default")
      (node (ref "IC7") (pin "10") (pinfunction "DSR_10") (pintype "bidirectional"))
    )
    (net (code "146") (name "unconnected-(IC7-RI-Pad11)") (class "Default")
      (node (ref "IC7") (pin "11") (pinfunction "RI_11") (pintype "bidirectional"))
    )
    (net (code "147") (name "unconnected-(IC7-RS232-Pad15)") (class "Default")
      (node (ref "IC7") (pin "15") (pinfunction "RS232_15") (pintype "bidirectional"))
    )
    (net (code "148") (name "unconnected-(IC7-RTS-Pad14)") (class "Default")
      (node (ref "IC7") (pin "14") (pinfunction "RTS_14") (pintype "bidirectional"))
    )
    (net (code "149") (name "unconnected-(J1-ID-Pad4)") (class "Default")
      (node (ref "J1") (pin "4") (pinfunction "ID_4") (pintype "bidirectional"))
    )
    (net (code "150") (name "unconnected-(J2-Pad5)") (class "Default")
      (node (ref "J2") (pin "5") (pinfunction "5_5") (pintype "passive"))
    )
    (net (code "151") (name "unconnected-(J2-Pad7)") (class "Default")
      (node (ref "J2") (pin "7") (pinfunction "7_7") (pintype "passive"))
    )
    (net (code "152") (name "unconnected-(J2-Pad9)") (class "Default")
      (node (ref "J2") (pin "9") (pinfunction "9_9") (pintype "passive"))
    )
    (net (code "153") (name "unconnected-(MICRO_SD1-CD-PadCD1)") (class "Default")
      (node (ref "MICRO_SD1") (pin "CD1") (pinfunction "CD_CD1") (pintype "passive"))
    )
    (net (code "154") (name "unconnected-(MICRO_SD1-DAT1-Pad8)") (class "Default")
      (node (ref "MICRO_SD1") (pin "8") (pinfunction "DAT1_8") (pintype "bidirectional"))
    )
    (net (code "155") (name "unconnected-(MICRO_SD1-DAT2-Pad1)") (class "Default")
      (node (ref "MICRO_SD1") (pin "1") (pinfunction "DAT2_1") (pintype "bidirectional"))
    )
    (net (code "156") (name "unconnected-(U1-(CLKO{slash}ICP3{slash}INT7)PE7-Pad9)") (class "Default")
      (node (ref "U1") (pin "9") (pinfunction "(CLKO/ICP3/INT7)PE7_9") (pintype "bidirectional"))
    )
    (net (code "157") (name "unconnected-(U1-(T1)PD6-Pad49)") (class "Default")
      (node (ref "U1") (pin "49") (pinfunction "(T1)PD6_49") (pintype "bidirectional"))
    )
    (net (code "158") (name "unconnected-(U1-(T3{slash}INT6)PE6-Pad8)") (class "Default")
      (node (ref "U1") (pin "8") (pinfunction "(T3/INT6)PE6_8") (pintype "bidirectional"))
    )
    (net (code "159") (name "unconnected-(U1-(TOSC1)PG4-Pad29)") (class "Default")
      (node (ref "U1") (pin "29") (pinfunction "(TOSC1)PG4_29") (pintype "bidirectional"))
    )
    (net (code "160") (name "unconnected-(U1-(XCK0{slash}AIN0)PE2-Pad4)") (class "Default")
      (node (ref "U1") (pin "4") (pinfunction "(XCK0/AIN0)PE2_4") (pintype "bidirectional"))
    )
    (net (code "161") (name "unconnected-(U1-PH2(XCK2)-Pad14)") (class "Default")
      (node (ref "U1") (pin "14") (pinfunction "PH2(XCK2)_14") (pintype "bidirectional"))
    )
    (net (code "162") (name "unconnected-(U1-PJ2(XCK3{slash}PCINT11)-Pad65)") (class "Default")
      (node (ref "U1") (pin "65") (pinfunction "PJ2(XCK3/PCINT11)_65") (pintype "bidirectional"))
    )
    (net (code "163") (name "unconnected-(U1-PJ3(PCINT12)-Pad66)") (class "Default")
      (node (ref "U1") (pin "66") (pinfunction "PJ3(PCINT12)_66") (pintype "bidirectional"))
    )
    (net (code "164") (name "unconnected-(U1-PJ4(PCINT13)-Pad67)") (class "Default")
      (node (ref "U1") (pin "67") (pinfunction "PJ4(PCINT13)_67") (pintype "bidirectional"))
    )
    (net (code "165") (name "{slash}BUSAK") (class "Default")
      (node (ref "18A") (pin "1") (pinfunction "P_1") (pintype "passive"))
    )
    (net (code "166") (name "{slash}BUSRQ") (class "Default")
      (node (ref "20A") (pin "1") (pinfunction "P_1") (pintype "passive"))
    )
    (net (code "167") (name "{slash}CLOCK") (class "Default")
      (node (ref "6B") (pin "1") (pinfunction "P_1") (pintype "passive"))
      (node (ref "IC4") (pin "22") (pinfunction "GCK1_22") (pintype "bidirectional"))
    )
    (net (code "168") (name "{slash}HALT") (class "Default")
      (node (ref "13A") (pin "1") (pinfunction "P_1") (pintype "passive"))
      (node (ref "SJ2") (pin "2") (pinfunction "2_2") (pintype "passive"))
    )
    (net (code "169") (name "{slash}IORQ") (class "Default")
      (node (ref "15A") (pin "1") (pinfunction "P_1") (pintype "passive"))
      (node (ref "IC4") (pin "43") (pinfunction "FB5MC14_43") (pintype "bidirectional"))
    )
    (net (code "170") (name "{slash}M1") (class "Default")
      (node (ref "22A") (pin "1") (pinfunction "P_1") (pintype "passive"))
      (node (ref "IC4") (pin "61") (pinfunction "FB7MC17_61") (pintype "bidirectional"))
    )
    (net (code "171") (name "{slash}MEM_CE") (class "Default")
      (node (ref "IC4") (pin "97") (pinfunction "FB4MC17_97") (pintype "bidirectional"))
      (node (ref "U1") (pin "50") (pinfunction "(T0)PD7_50") (pintype "bidirectional"))
      (node (ref "U2") (pin "22") (pinfunction "CE_22") (pintype "input"))
    )
    (net (code "172") (name "{slash}MEM_OE") (class "Default")
      (node (ref "IC4") (pin "12") (pinfunction "FB1MC3_12") (pintype "bidirectional"))
      (node (ref "U1") (pin "52") (pinfunction "(RD)PG1_52") (pintype "bidirectional"))
      (node (ref "U2") (pin "24") (pinfunction "OE_24") (pintype "input"))
    )
    (net (code "173") (name "{slash}MREQ") (class "Default")
      (node (ref "14A") (pin "1") (pinfunction "P_1") (pintype "passive"))
      (node (ref "IC4") (pin "41") (pinfunction "FB5MC11_41") (pintype "bidirectional"))
    )
    (net (code "174") (name "{slash}NMI") (class "Default")
      (node (ref "12A") (pin "1") (pinfunction "P_1") (pintype "passive"))
      (node (ref "IC4") (pin "36") (pinfunction "FB5MC5_36") (pintype "bidirectional"))
    )
    (net (code "175") (name "{slash}OE_CTRL_CLOCK") (class "Default")
      (node (ref "IC3") (pin "10") (pinfunction "OE_10") (pintype "input"))
      (node (ref "IC4") (pin "10") (pinfunction "FB2MC17_10") (pintype "bidirectional"))
    )
    (net (code "176") (name "{slash}OE_IL") (class "Default")
      (node (ref "IC4") (pin "15") (pinfunction "FB1MC8_15") (pintype "bidirectional"))
      (node (ref "IC5") (pin "1") (pinfunction "OC_1") (pintype "input"))
    )
    (net (code "177") (name "{slash}OE_RAMCS") (class "Default")
      (node (ref "IC3") (pin "4") (pinfunction "OE_4") (pintype "input"))
      (node (ref "IC4") (pin "17") (pinfunction "FB1MC11_17") (pintype "bidirectional"))
    )
    (net (code "178") (name "{slash}OE_ROMCS") (class "Default")
      (node (ref "IC3") (pin "1") (pinfunction "OE_1") (pintype "input"))
      (node (ref "IC4") (pin "14") (pinfunction "FB1MC6_14") (pintype "bidirectional"))
    )
    (net (code "179") (name "{slash}RAMCS") (class "Default")
      (node (ref "2A") (pin "1") (pinfunction "P_1") (pintype "passive"))
      (node (ref "IC3") (pin "6") (pinfunction "O_6") (pintype "tri_state"))
    )
    (net (code "180") (name "{slash}RD") (class "Default")
      (node (ref "16A") (pin "1") (pinfunction "P_1") (pintype "passive"))
      (node (ref "IC4") (pin "49") (pinfunction "FB5MC17_49") (pintype "bidirectional"))
    )
    (net (code "181") (name "{slash}RESET") (class "Default")
      (node (ref "21A") (pin "1") (pinfunction "P_1") (pintype "passive"))
      (node (ref "IC4") (pin "71") (pinfunction "FB8MC14_71") (pintype "bidirectional"))
      (node (ref "U1") (pin "15") (pinfunction "PH3(OC4A)_15") (pintype "bidirectional"))
    )
    (net (code "182") (name "{slash}RFSH") (class "Default")
      (node (ref "23A") (pin "1") (pinfunction "P_1") (pintype "passive"))
      (node (ref "IC4") (pin "64") (pinfunction "FB8MC5_64") (pintype "bidirectional"))
    )
    (net (code "183") (name "{slash}ROMCS") (class "Default")
      (node (ref "23B") (pin "1") (pinfunction "P_1") (pintype "passive"))
      (node (ref "IC3") (pin "3") (pinfunction "O_3") (pintype "tri_state"))
    )
    (net (code "184") (name "{slash}WAIT") (class "Default")
      (node (ref "19A") (pin "1") (pinfunction "P_1") (pintype "passive"))
      (node (ref "IC4") (pin "56") (pinfunction "FB7MC11_56") (pintype "bidirectional"))
      (node (ref "U1") (pin "42") (pinfunction "PL7_42") (pintype "bidirectional"))
    )
    (net (code "185") (name "{slash}WR") (class "Default")
      (node (ref "17A") (pin "1") (pinfunction "P_1") (pintype "passive"))
      (node (ref "IC4") (pin "52") (pinfunction "FB7MC5_52") (pintype "bidirectional"))
    )
    (net (code "186") (name "{slash}WR'") (class "Default")
      (node (ref "IC4") (pin "13") (pinfunction "FB1MC5_13") (pintype "bidirectional"))
      (node (ref "U1") (pin "51") (pinfunction "(WR)PG0_51") (pintype "bidirectional"))
      (node (ref "U2") (pin "29") (pinfunction "WE_29") (pintype "input"))
    )
  )
)
